# ADC3_FPGA_BGA.net
KiCad netlist of a schematic drawn in EAGLE
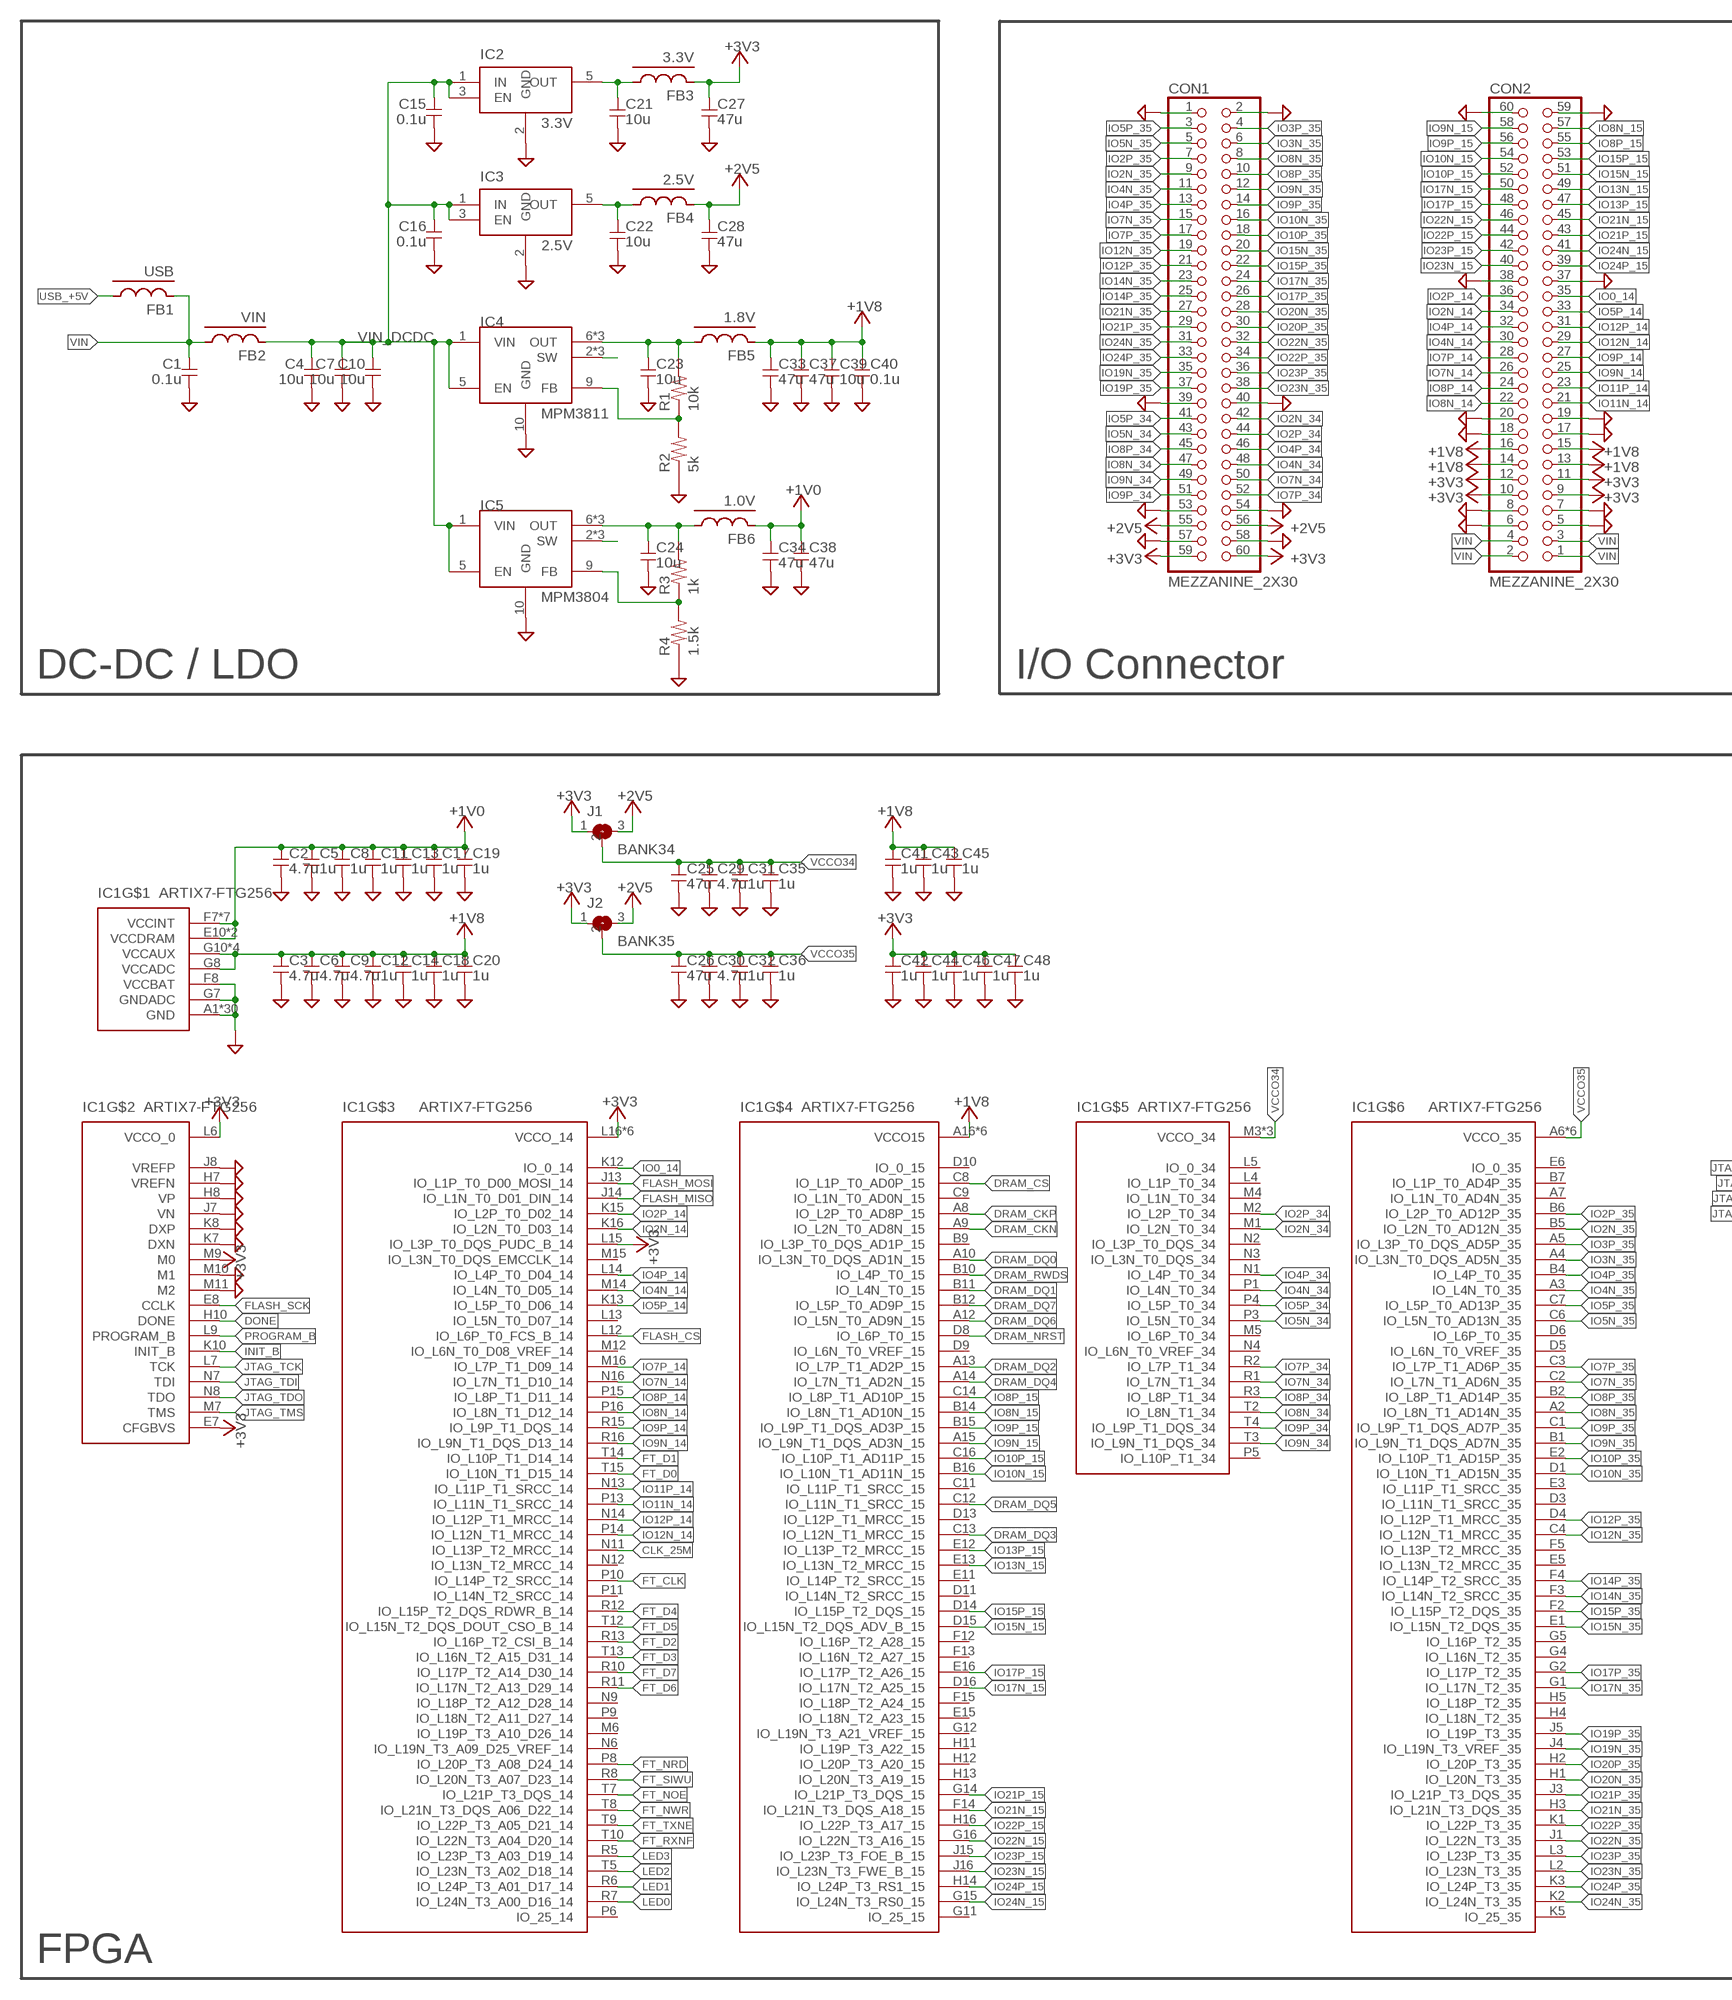
[diagram p0: schematic, sheet 1, part 1 of 2]
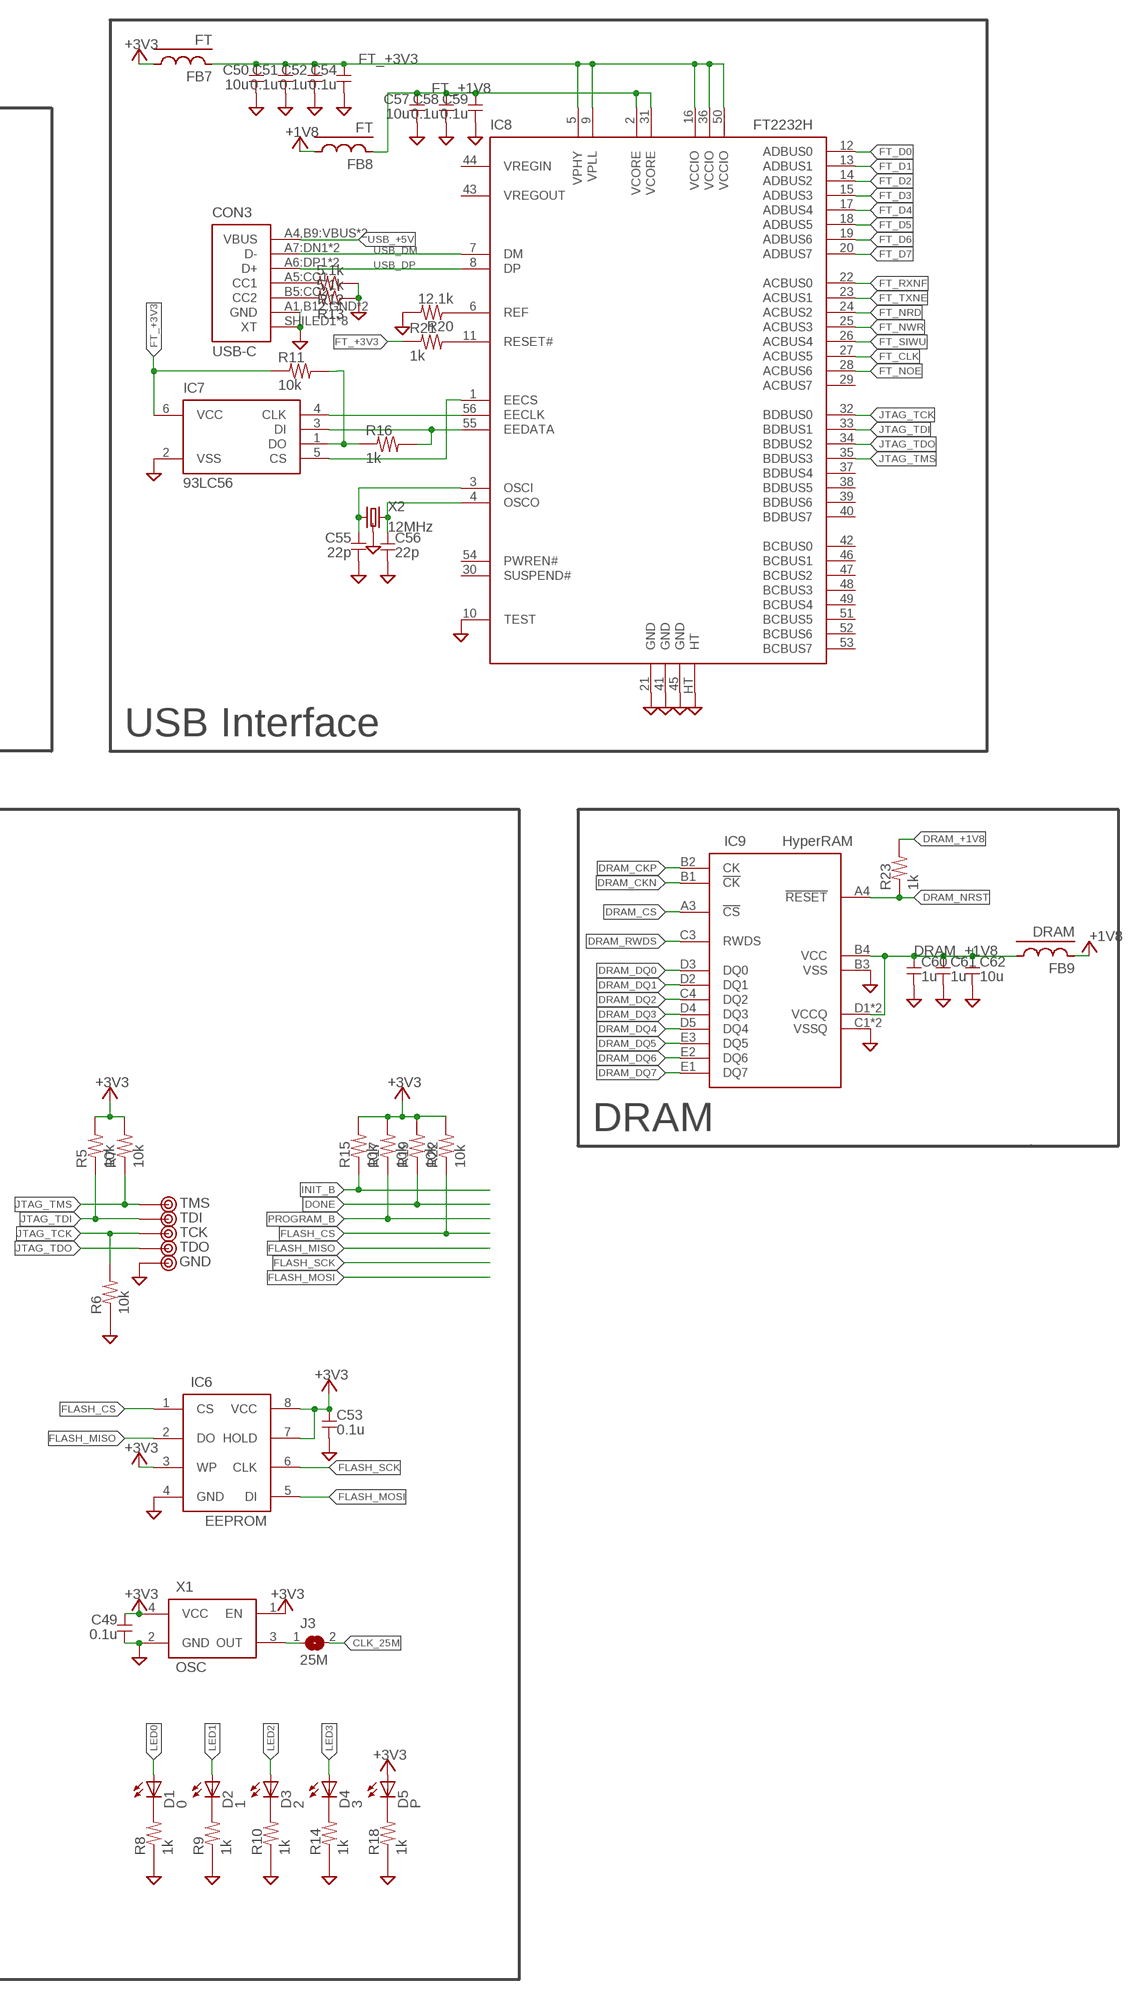
[diagram p1: schematic, sheet 1, part 2 of 2]

(export (version "E")
  (design (tool "Eeschema 10.0.6"))
  (components
    (comp (ref "C1")
      (value "0.1u")
      (footprint "eagle-import:1608C")
      (libsource (lib "eagle-import") (part "C-1608"))
    )
    (comp (ref "C2")
      (value "4.7u")
      (footprint "eagle-import:1608C")
      (libsource (lib "eagle-import") (part "C-1608"))
    )
    (comp (ref "C3")
      (value "4.7u")
      (footprint "eagle-import:1608C")
      (libsource (lib "eagle-import") (part "C-1608"))
    )
    (comp (ref "C4")
      (value "10u")
      (footprint "eagle-import:2012")
      (libsource (lib "eagle-import") (part "C-2012"))
    )
    (comp (ref "C5")
      (value "1u")
      (footprint "eagle-import:1005")
      (libsource (lib "eagle-import") (part "C-1005"))
    )
    (comp (ref "C6")
      (value "4.7u")
      (footprint "eagle-import:1608C")
      (libsource (lib "eagle-import") (part "C-1608"))
    )
    (comp (ref "C7")
      (value "10u")
      (footprint "eagle-import:1608C")
      (libsource (lib "eagle-import") (part "C-1608"))
    )
    (comp (ref "C8")
      (value "1u")
      (footprint "eagle-import:1005")
      (libsource (lib "eagle-import") (part "C-1005"))
    )
    (comp (ref "C9")
      (value "4.7u")
      (footprint "eagle-import:1608C")
      (libsource (lib "eagle-import") (part "C-1608"))
    )
    (comp (ref "C10")
      (value "10u")
      (footprint "eagle-import:1608C")
      (libsource (lib "eagle-import") (part "C-1608"))
    )
    (comp (ref "C11")
      (value "1u")
      (footprint "eagle-import:1005")
      (libsource (lib "eagle-import") (part "C-1005"))
    )
    (comp (ref "C12")
      (value "1u")
      (footprint "eagle-import:1005")
      (libsource (lib "eagle-import") (part "C-1005"))
    )
    (comp (ref "C13")
      (value "1u")
      (footprint "eagle-import:1005")
      (libsource (lib "eagle-import") (part "C-1005"))
    )
    (comp (ref "C14")
      (value "1u")
      (footprint "eagle-import:1005")
      (libsource (lib "eagle-import") (part "C-1005"))
    )
    (comp (ref "C15")
      (value "0.1u")
      (footprint "eagle-import:1608C")
      (libsource (lib "eagle-import") (part "C-1608"))
    )
    (comp (ref "C16")
      (value "0.1u")
      (footprint "eagle-import:1608C")
      (libsource (lib "eagle-import") (part "C-1608"))
    )
    (comp (ref "C17")
      (value "1u")
      (footprint "eagle-import:1005")
      (libsource (lib "eagle-import") (part "C-1005"))
    )
    (comp (ref "C18")
      (value "1u")
      (footprint "eagle-import:1005")
      (libsource (lib "eagle-import") (part "C-1005"))
    )
    (comp (ref "C19")
      (value "1u")
      (footprint "eagle-import:1005")
      (libsource (lib "eagle-import") (part "C-1005"))
    )
    (comp (ref "C20")
      (value "1u")
      (footprint "eagle-import:1005")
      (libsource (lib "eagle-import") (part "C-1005"))
    )
    (comp (ref "C21")
      (value "10u")
      (footprint "eagle-import:1608C")
      (libsource (lib "eagle-import") (part "C-1608"))
    )
    (comp (ref "C22")
      (value "10u")
      (footprint "eagle-import:1608C")
      (libsource (lib "eagle-import") (part "C-1608"))
    )
    (comp (ref "C23")
      (value "10u")
      (footprint "eagle-import:1608C")
      (libsource (lib "eagle-import") (part "C-1608"))
    )
    (comp (ref "C24")
      (value "10u")
      (footprint "eagle-import:1608C")
      (libsource (lib "eagle-import") (part "C-1608"))
    )
    (comp (ref "C25")
      (value "47u")
      (footprint "eagle-import:2012")
      (libsource (lib "eagle-import") (part "C-2012"))
    )
    (comp (ref "C26")
      (value "47u")
      (footprint "eagle-import:2012")
      (libsource (lib "eagle-import") (part "C-2012"))
    )
    (comp (ref "C27")
      (value "47u")
      (footprint "eagle-import:2012")
      (libsource (lib "eagle-import") (part "C-2012"))
    )
    (comp (ref "C28")
      (value "47u")
      (footprint "eagle-import:2012")
      (libsource (lib "eagle-import") (part "C-2012"))
    )
    (comp (ref "C29")
      (value "4.7u")
      (footprint "eagle-import:1608C")
      (libsource (lib "eagle-import") (part "C-1608"))
    )
    (comp (ref "C30")
      (value "4.7u")
      (footprint "eagle-import:1608C")
      (libsource (lib "eagle-import") (part "C-1608"))
    )
    (comp (ref "C31")
      (value "1u")
      (footprint "eagle-import:1005")
      (libsource (lib "eagle-import") (part "C-1005"))
    )
    (comp (ref "C32")
      (value "1u")
      (footprint "eagle-import:1005")
      (libsource (lib "eagle-import") (part "C-1005"))
    )
    (comp (ref "C33")
      (value "47u")
      (footprint "eagle-import:2012")
      (libsource (lib "eagle-import") (part "C-2012"))
    )
    (comp (ref "C34")
      (value "47u")
      (footprint "eagle-import:2012")
      (libsource (lib "eagle-import") (part "C-2012"))
    )
    (comp (ref "C35")
      (value "1u")
      (footprint "eagle-import:1005")
      (libsource (lib "eagle-import") (part "C-1005"))
    )
    (comp (ref "C36")
      (value "1u")
      (footprint "eagle-import:1005")
      (libsource (lib "eagle-import") (part "C-1005"))
    )
    (comp (ref "C37")
      (value "47u")
      (footprint "eagle-import:2012")
      (libsource (lib "eagle-import") (part "C-2012"))
    )
    (comp (ref "C38")
      (value "47u")
      (footprint "eagle-import:2012")
      (libsource (lib "eagle-import") (part "C-2012"))
    )
    (comp (ref "C39")
      (value "10u")
      (footprint "eagle-import:3216")
      (libsource (lib "eagle-import") (part "C-3216"))
    )
    (comp (ref "C40")
      (value "0.1u")
      (footprint "eagle-import:1608C")
      (libsource (lib "eagle-import") (part "C-1608"))
    )
    (comp (ref "C41")
      (value "1u")
      (footprint "eagle-import:1005")
      (libsource (lib "eagle-import") (part "C-1005"))
    )
    (comp (ref "C42")
      (value "1u")
      (footprint "eagle-import:1005")
      (libsource (lib "eagle-import") (part "C-1005"))
    )
    (comp (ref "C43")
      (value "1u")
      (footprint "eagle-import:1005")
      (libsource (lib "eagle-import") (part "C-1005"))
    )
    (comp (ref "C44")
      (value "1u")
      (footprint "eagle-import:1005")
      (libsource (lib "eagle-import") (part "C-1005"))
    )
    (comp (ref "C45")
      (value "1u")
      (footprint "eagle-import:1005")
      (libsource (lib "eagle-import") (part "C-1005"))
    )
    (comp (ref "C46")
      (value "1u")
      (footprint "eagle-import:1005")
      (libsource (lib "eagle-import") (part "C-1005"))
    )
    (comp (ref "C47")
      (value "1u")
      (footprint "eagle-import:1005")
      (libsource (lib "eagle-import") (part "C-1005"))
    )
    (comp (ref "C48")
      (value "1u")
      (footprint "eagle-import:1005")
      (libsource (lib "eagle-import") (part "C-1005"))
    )
    (comp (ref "C49")
      (value "0.1u")
      (footprint "eagle-import:1608C")
      (libsource (lib "eagle-import") (part "C-1608"))
    )
    (comp (ref "C50")
      (value "10u")
      (footprint "eagle-import:1608C")
      (libsource (lib "eagle-import") (part "C-1608"))
    )
    (comp (ref "C51")
      (value "0.1u")
      (footprint "eagle-import:1608C")
      (libsource (lib "eagle-import") (part "C-1608"))
    )
    (comp (ref "C52")
      (value "0.1u")
      (footprint "eagle-import:1608C")
      (libsource (lib "eagle-import") (part "C-1608"))
    )
    (comp (ref "C53")
      (value "0.1u")
      (footprint "eagle-import:1608C")
      (libsource (lib "eagle-import") (part "C-1608"))
    )
    (comp (ref "C54")
      (value "0.1u")
      (footprint "eagle-import:1608C")
      (libsource (lib "eagle-import") (part "C-1608"))
    )
    (comp (ref "C55")
      (value "22p")
      (footprint "eagle-import:1608C")
      (libsource (lib "eagle-import") (part "C-1608"))
    )
    (comp (ref "C56")
      (value "22p")
      (footprint "eagle-import:1608C")
      (libsource (lib "eagle-import") (part "C-1608"))
    )
    (comp (ref "C57")
      (value "10u")
      (footprint "eagle-import:1608C")
      (libsource (lib "eagle-import") (part "C-1608"))
    )
    (comp (ref "C58")
      (value "0.1u")
      (footprint "eagle-import:1608C")
      (libsource (lib "eagle-import") (part "C-1608"))
    )
    (comp (ref "C59")
      (value "0.1u")
      (footprint "eagle-import:1608C")
      (libsource (lib "eagle-import") (part "C-1608"))
    )
    (comp (ref "C60")
      (value "1u")
      (footprint "eagle-import:1608C")
      (libsource (lib "eagle-import") (part "C-1608"))
    )
    (comp (ref "C61")
      (value "1u")
      (footprint "eagle-import:1608C")
      (libsource (lib "eagle-import") (part "C-1608"))
    )
    (comp (ref "C62")
      (value "10u")
      (footprint "eagle-import:2012")
      (libsource (lib "eagle-import") (part "C-2012"))
    )
    (comp (ref "CON1")
      (value "MEZZANINE_2X30")
      (footprint "eagle-import:MEZZANINE_0.8MM_2X30")
      (libsource (lib "eagle-import") (part "MEZZANINE_2X30"))
    )
    (comp (ref "CON2")
      (value "MEZZANINE_2X30")
      (footprint "eagle-import:MEZZANINE_0.8MM_2X30")
      (libsource (lib "eagle-import") (part "MEZZANINE_2X30"))
    )
    (comp (ref "CON3")
      (value "USB-C")
      (footprint "eagle-import:5077CR-16-SMC2-BK-TR")
      (libsource (lib "eagle-import") (part "USB-C"))
    )
    (comp (ref "D1")
      (value "0")
      (footprint "eagle-import:D1608")
      (libsource (lib "eagle-import") (part "LED-SMD1608"))
    )
    (comp (ref "D2")
      (value "1")
      (footprint "eagle-import:D1608")
      (libsource (lib "eagle-import") (part "LED-SMD1608"))
    )
    (comp (ref "D3")
      (value "2")
      (footprint "eagle-import:D1608")
      (libsource (lib "eagle-import") (part "LED-SMD1608"))
    )
    (comp (ref "D4")
      (value "3")
      (footprint "eagle-import:D1608")
      (libsource (lib "eagle-import") (part "LED-SMD1608"))
    )
    (comp (ref "D5")
      (value "P")
      (footprint "eagle-import:D1608")
      (libsource (lib "eagle-import") (part "LED-SMD1608"))
    )
    (comp (ref "FB1")
      (value "USB")
      (footprint "eagle-import:1608-J")
      (libsource (lib "eagle-import") (part "FB"))
    )
    (comp (ref "FB2")
      (value "VIN")
      (footprint "eagle-import:1608-J")
      (libsource (lib "eagle-import") (part "FB"))
    )
    (comp (ref "FB3")
      (value "3.3V")
      (footprint "eagle-import:1608-J")
      (libsource (lib "eagle-import") (part "FB"))
    )
    (comp (ref "FB4")
      (value "2.5V")
      (footprint "eagle-import:1608-J")
      (libsource (lib "eagle-import") (part "FB"))
    )
    (comp (ref "FB5")
      (value "1.8V")
      (footprint "eagle-import:1608-J")
      (libsource (lib "eagle-import") (part "FB"))
    )
    (comp (ref "FB6")
      (value "1.0V")
      (footprint "eagle-import:1608-J")
      (libsource (lib "eagle-import") (part "FB"))
    )
    (comp (ref "FB7")
      (value "FT")
      (footprint "eagle-import:1608-J")
      (libsource (lib "eagle-import") (part "FB"))
    )
    (comp (ref "FB8")
      (value "FT")
      (footprint "eagle-import:1608-J")
      (libsource (lib "eagle-import") (part "FB"))
    )
    (comp (ref "FB9")
      (value "DRAM")
      (footprint "eagle-import:1608-J")
      (libsource (lib "eagle-import") (part "FB"))
    )
    (comp (ref "IC1")
      (value "ARTIX7-FTG256")
      (footprint "eagle-import:FTG256")
      (libsource (lib "eagle-import") (part "ARTIX7-FTG256"))
    )
    (comp (ref "IC2")
      (value "3.3V")
      (footprint "eagle-import:SOT23-5")
      (libsource (lib "eagle-import") (part "TLV740"))
    )
    (comp (ref "IC3")
      (value "2.5V")
      (footprint "eagle-import:SOT23-5")
      (libsource (lib "eagle-import") (part "TLV740"))
    )
    (comp (ref "IC4")
      (value "MPM3811")
      (footprint "eagle-import:QFN-10")
      (libsource (lib "eagle-import") (part "MPM3804"))
    )
    (comp (ref "IC5")
      (value "MPM3804")
      (footprint "eagle-import:QFN-10")
      (libsource (lib "eagle-import") (part "MPM3804"))
    )
    (comp (ref "IC6")
      (value "EEPROM")
      (footprint "eagle-import:SOIC-SOIJ-8")
      (libsource (lib "eagle-import") (part "EEPROM_SPI-WIDE"))
    )
    (comp (ref "IC7")
      (value "93LC56")
      (footprint "eagle-import:SOT23-6")
      (libsource (lib "eagle-import") (part "93LC56"))
    )
    (comp (ref "IC8")
      (value "FT2232H")
      (footprint "eagle-import:QFN56-HT")
      (libsource (lib "eagle-import") (part "FT2232H-2"))
    )
    (comp (ref "IC9")
      (value "HyperRAM")
      (footprint "eagle-import:TFBGA24")
      (libsource (lib "eagle-import") (part "HYPERRAM"))
    )
    (comp (ref "J1")
      (value "BANK34")
      (footprint "eagle-import:1608-3-J")
      (libsource (lib "eagle-import") (part "SJ-3-1608"))
    )
    (comp (ref "J2")
      (value "BANK35")
      (footprint "eagle-import:1608-3-J")
      (libsource (lib "eagle-import") (part "SJ-3-1608"))
    )
    (comp (ref "J3")
      (value "25M")
      (footprint "eagle-import:1608-J")
      (libsource (lib "eagle-import") (part "SJ-1608"))
    )
    (comp (ref "R1")
      (value "10k")
      (footprint "eagle-import:1608")
      (libsource (lib "eagle-import") (part "R-1608"))
    )
    (comp (ref "R2")
      (value "5k")
      (footprint "eagle-import:1608")
      (libsource (lib "eagle-import") (part "R-1608"))
    )
    (comp (ref "R3")
      (value "1k")
      (footprint "eagle-import:1608")
      (libsource (lib "eagle-import") (part "R-1608"))
    )
    (comp (ref "R4")
      (value "1.5k")
      (footprint "eagle-import:1608")
      (libsource (lib "eagle-import") (part "R-1608"))
    )
    (comp (ref "R5")
      (value "10k")
      (footprint "eagle-import:1608")
      (libsource (lib "eagle-import") (part "R-1608"))
    )
    (comp (ref "R6")
      (value "10k")
      (footprint "eagle-import:1608")
      (libsource (lib "eagle-import") (part "R-1608"))
    )
    (comp (ref "R7")
      (value "10k")
      (footprint "eagle-import:1608")
      (libsource (lib "eagle-import") (part "R-1608"))
    )
    (comp (ref "R8")
      (value "1k")
      (footprint "eagle-import:1608")
      (libsource (lib "eagle-import") (part "R-1608"))
    )
    (comp (ref "R9")
      (value "1k")
      (footprint "eagle-import:1608")
      (libsource (lib "eagle-import") (part "R-1608"))
    )
    (comp (ref "R10")
      (value "1k")
      (footprint "eagle-import:1608")
      (libsource (lib "eagle-import") (part "R-1608"))
    )
    (comp (ref "R11")
      (value "10k")
      (footprint "eagle-import:1608")
      (libsource (lib "eagle-import") (part "R-1608"))
    )
    (comp (ref "R12")
      (value "5.1k")
      (footprint "eagle-import:1608")
      (libsource (lib "eagle-import") (part "R-1608"))
    )
    (comp (ref "R13")
      (value "5.1k")
      (footprint "eagle-import:1608")
      (libsource (lib "eagle-import") (part "R-1608"))
    )
    (comp (ref "R14")
      (value "1k")
      (footprint "eagle-import:1608")
      (libsource (lib "eagle-import") (part "R-1608"))
    )
    (comp (ref "R15")
      (value "10k")
      (footprint "eagle-import:1608")
      (libsource (lib "eagle-import") (part "R-1608"))
    )
    (comp (ref "R16")
      (value "1k")
      (footprint "eagle-import:1608")
      (libsource (lib "eagle-import") (part "R-1608"))
    )
    (comp (ref "R17")
      (value "10k")
      (footprint "eagle-import:1608")
      (libsource (lib "eagle-import") (part "R-1608"))
    )
    (comp (ref "R18")
      (value "1k")
      (footprint "eagle-import:1608")
      (libsource (lib "eagle-import") (part "R-1608"))
    )
    (comp (ref "R19")
      (value "10k")
      (footprint "eagle-import:1608")
      (libsource (lib "eagle-import") (part "R-1608"))
    )
    (comp (ref "R20")
      (value "12.1k")
      (footprint "eagle-import:1608")
      (libsource (lib "eagle-import") (part "R-1608"))
    )
    (comp (ref "R21")
      (value "1k")
      (footprint "eagle-import:1608")
      (libsource (lib "eagle-import") (part "R-1608"))
    )
    (comp (ref "R22")
      (value "10k")
      (footprint "eagle-import:1608")
      (libsource (lib "eagle-import") (part "R-1608"))
    )
    (comp (ref "R23")
      (value "1k")
      (footprint "eagle-import:1608")
      (libsource (lib "eagle-import") (part "R-1608"))
    )
    (comp (ref "TP1")
      (value "TMS")
      (footprint "eagle-import:TESTPAD-SMALL")
      (libsource (lib "eagle-import") (part "TESTPIN-PAD-SMALL"))
    )
    (comp (ref "TP2")
      (value "TDI")
      (footprint "eagle-import:TESTPAD-SMALL")
      (libsource (lib "eagle-import") (part "TESTPIN-PAD-SMALL"))
    )
    (comp (ref "TP3")
      (value "TCK")
      (footprint "eagle-import:TESTPAD-SMALL")
      (libsource (lib "eagle-import") (part "TESTPIN-PAD-SMALL"))
    )
    (comp (ref "TP4")
      (value "TDO")
      (footprint "eagle-import:TESTPAD-SMALL")
      (libsource (lib "eagle-import") (part "TESTPIN-PAD-SMALL"))
    )
    (comp (ref "TP5")
      (value "GND")
      (footprint "eagle-import:TESTPAD-SMALL")
      (libsource (lib "eagle-import") (part "TESTPIN-PAD-SMALL"))
    )
    (comp (ref "X1")
      (value "OSC")
      (footprint "eagle-import:KC3225")
      (libsource (lib "eagle-import") (part "OSC-KC3225"))
    )
    (comp (ref "X2")
      (value "12MHz")
      (footprint "eagle-import:KC3225")
      (libsource (lib "eagle-import") (part "CRYSTAL2"))
    )
  )
  (nets
    (net (code "1") (name "+1V0") (class "Default")
      (node (ref "C11") (pin "1") (pinfunction "1_1") (pintype "passive"))
      (node (ref "C13") (pin "1") (pinfunction "1_1") (pintype "passive"))
      (node (ref "C17") (pin "1") (pinfunction "1_1") (pintype "passive"))
      (node (ref "C19") (pin "1") (pinfunction "1_1") (pintype "passive"))
      (node (ref "C2") (pin "1") (pinfunction "1_1") (pintype "passive"))
      (node (ref "C34") (pin "1") (pinfunction "1_1") (pintype "passive"))
      (node (ref "C38") (pin "1") (pinfunction "1_1") (pintype "passive"))
      (node (ref "C5") (pin "1") (pinfunction "1_1") (pintype "passive"))
      (node (ref "C8") (pin "1") (pinfunction "1_1") (pintype "passive"))
      (node (ref "FB6") (pin "2") (pinfunction "2_2") (pintype "passive"))
      (node (ref "IC1") (pin "E10") (pinfunction "VCCDRAM_E10") (pintype "input"))
      (node (ref "IC1") (pin "F11") (pinfunction "VCCDRAM_F11") (pintype "input"))
      (node (ref "IC1") (pin "F7") (pinfunction "VCCINT_F7") (pintype "input"))
      (node (ref "IC1") (pin "F9") (pinfunction "VCCINT_F9") (pintype "input"))
      (node (ref "IC1") (pin "G6") (pinfunction "VCCINT_G6") (pintype "input"))
      (node (ref "IC1") (pin "H9") (pinfunction "VCCINT_H9") (pintype "input"))
      (node (ref "IC1") (pin "J6") (pinfunction "VCCINT_J6") (pintype "input"))
      (node (ref "IC1") (pin "K9") (pinfunction "VCCINT_K9") (pintype "input"))
      (node (ref "IC1") (pin "L8") (pinfunction "VCCINT_L8") (pintype "input"))
    )
    (net (code "2") (name "+1V8") (class "Default")
      (node (ref "C12") (pin "1") (pinfunction "1_1") (pintype "passive"))
      (node (ref "C14") (pin "1") (pinfunction "1_1") (pintype "passive"))
      (node (ref "C18") (pin "1") (pinfunction "1_1") (pintype "passive"))
      (node (ref "C20") (pin "1") (pinfunction "1_1") (pintype "passive"))
      (node (ref "C3") (pin "1") (pinfunction "1_1") (pintype "passive"))
      (node (ref "C33") (pin "1") (pinfunction "1_1") (pintype "passive"))
      (node (ref "C37") (pin "1") (pinfunction "1_1") (pintype "passive"))
      (node (ref "C39") (pin "1") (pinfunction "1_1") (pintype "passive"))
      (node (ref "C40") (pin "1") (pinfunction "1_1") (pintype "passive"))
      (node (ref "C41") (pin "1") (pinfunction "1_1") (pintype "passive"))
      (node (ref "C43") (pin "1") (pinfunction "1_1") (pintype "passive"))
      (node (ref "C45") (pin "1") (pinfunction "1_1") (pintype "passive"))
      (node (ref "C6") (pin "1") (pinfunction "1_1") (pintype "passive"))
      (node (ref "C9") (pin "1") (pinfunction "1_1") (pintype "passive"))
      (node (ref "CON2") (pin "13") (pinfunction "13_13") (pintype "passive"))
      (node (ref "CON2") (pin "14") (pinfunction "14_14") (pintype "passive"))
      (node (ref "CON2") (pin "15") (pinfunction "15_15") (pintype "passive"))
      (node (ref "CON2") (pin "16") (pinfunction "16_16") (pintype "passive"))
      (node (ref "FB5") (pin "2") (pinfunction "2_2") (pintype "passive"))
      (node (ref "FB8") (pin "1") (pinfunction "1_1") (pintype "passive"))
      (node (ref "FB9") (pin "2") (pinfunction "2_2") (pintype "passive"))
      (node (ref "IC1") (pin "A16") (pinfunction "VCCO15_A16") (pintype "input"))
      (node (ref "IC1") (pin "B13") (pinfunction "VCCO15_B13") (pintype "input"))
      (node (ref "IC1") (pin "C10") (pinfunction "VCCO15_C10") (pintype "input"))
      (node (ref "IC1") (pin "E14") (pinfunction "VCCO15_E14") (pintype "input"))
      (node (ref "IC1") (pin "G10") (pinfunction "VCCAUX_G10") (pintype "input"))
      (node (ref "IC1") (pin "G8") (pinfunction "VCCADC_G8") (pintype "input"))
      (node (ref "IC1") (pin "H15") (pinfunction "VCCO15_H15") (pintype "input"))
      (node (ref "IC1") (pin "J10") (pinfunction "VCCAUX_J10") (pintype "input"))
      (node (ref "IC1") (pin "J12") (pinfunction "VCCO15_J12") (pintype "input"))
      (node (ref "IC1") (pin "K11") (pinfunction "VCCAUX_K11") (pintype "input"))
      (node (ref "IC1") (pin "L10") (pinfunction "VCCAUX_L10") (pintype "input"))
    )
    (net (code "3") (name "+2V5") (class "Default")
      (node (ref "C28") (pin "1") (pinfunction "1_1") (pintype "passive"))
      (node (ref "CON1") (pin "55") (pinfunction "55_55") (pintype "passive"))
      (node (ref "CON1") (pin "56") (pinfunction "56_56") (pintype "passive"))
      (node (ref "FB4") (pin "2") (pinfunction "2_2") (pintype "passive"))
      (node (ref "J1") (pin "3") (pinfunction "3_3") (pintype "passive"))
      (node (ref "J2") (pin "3") (pinfunction "3_3") (pintype "passive"))
    )
    (net (code "4") (name "+3V3") (class "Default")
      (node (ref "C27") (pin "1") (pinfunction "1_1") (pintype "passive"))
      (node (ref "C42") (pin "1") (pinfunction "1_1") (pintype "passive"))
      (node (ref "C44") (pin "1") (pinfunction "1_1") (pintype "passive"))
      (node (ref "C46") (pin "1") (pinfunction "1_1") (pintype "passive"))
      (node (ref "C47") (pin "1") (pinfunction "1_1") (pintype "passive"))
      (node (ref "C48") (pin "1") (pinfunction "1_1") (pintype "passive"))
      (node (ref "C49") (pin "1") (pinfunction "1_1") (pintype "passive"))
      (node (ref "C53") (pin "1") (pinfunction "1_1") (pintype "passive"))
      (node (ref "CON1") (pin "59") (pinfunction "59_59") (pintype "passive"))
      (node (ref "CON1") (pin "60") (pinfunction "60_60") (pintype "passive"))
      (node (ref "CON2") (pin "10") (pinfunction "10_10") (pintype "passive"))
      (node (ref "CON2") (pin "11") (pinfunction "11_11") (pintype "passive"))
      (node (ref "CON2") (pin "12") (pinfunction "12_12") (pintype "passive"))
      (node (ref "CON2") (pin "9") (pinfunction "9_9") (pintype "passive"))
      (node (ref "D5") (pin "A") (pinfunction "A_A") (pintype "passive"))
      (node (ref "FB3") (pin "2") (pinfunction "2_2") (pintype "passive"))
      (node (ref "FB7") (pin "1") (pinfunction "1_1") (pintype "passive"))
      (node (ref "IC1") (pin "E7") (pinfunction "CFGBVS_E7") (pintype "bidirectional"))
      (node (ref "IC1") (pin "L15") (pinfunction "IO_L3P_T0_DQS_PUDC_B_14_L15") (pintype "bidirectional"))
      (node (ref "IC1") (pin "L16") (pinfunction "VCCO_14_L16") (pintype "input"))
      (node (ref "IC1") (pin "L6") (pinfunction "VCCO_0_L6") (pintype "bidirectional"))
      (node (ref "IC1") (pin "M13") (pinfunction "VCCO_14_M13") (pintype "input"))
      (node (ref "IC1") (pin "M9") (pinfunction "M0_M9") (pintype "bidirectional"))
      (node (ref "IC1") (pin "N10") (pinfunction "VCCO_14_N10") (pintype "input"))
      (node (ref "IC1") (pin "P7") (pinfunction "VCCO_14_P7") (pintype "input"))
      (node (ref "IC1") (pin "R14") (pinfunction "VCCO_14_R14") (pintype "input"))
      (node (ref "IC1") (pin "T11") (pinfunction "VCCO_14_T11") (pintype "input"))
      (node (ref "IC6") (pin "3") (pinfunction "WP_3") (pintype "input"))
      (node (ref "IC6") (pin "7") (pinfunction "HOLD_7") (pintype "input"))
      (node (ref "IC6") (pin "8") (pinfunction "VCC_8") (pintype "input"))
      (node (ref "J1") (pin "1") (pinfunction "1_1") (pintype "passive"))
      (node (ref "J2") (pin "1") (pinfunction "1_1") (pintype "passive"))
      (node (ref "R15") (pin "2") (pinfunction "2_2") (pintype "passive"))
      (node (ref "R17") (pin "2") (pinfunction "2_2") (pintype "passive"))
      (node (ref "R19") (pin "2") (pinfunction "2_2") (pintype "passive"))
      (node (ref "R22") (pin "2") (pinfunction "2_2") (pintype "passive"))
      (node (ref "R5") (pin "2") (pinfunction "2_2") (pintype "passive"))
      (node (ref "R7") (pin "2") (pinfunction "2_2") (pintype "passive"))
      (node (ref "X1") (pin "1") (pinfunction "EN_1") (pintype "input"))
      (node (ref "X1") (pin "4") (pinfunction "VCC_4") (pintype "input"))
    )
    (net (code "5") (name "/FT_+1V8") (class "Default")
      (node (ref "C57") (pin "1") (pinfunction "1_1") (pintype "passive"))
      (node (ref "C58") (pin "1") (pinfunction "1_1") (pintype "passive"))
      (node (ref "C59") (pin "1") (pinfunction "1_1") (pintype "passive"))
      (node (ref "FB8") (pin "2") (pinfunction "2_2") (pintype "passive"))
      (node (ref "IC8") (pin "2") (pinfunction "VCORE_2") (pintype "input"))
      (node (ref "IC8") (pin "31") (pinfunction "VCORE_31") (pintype "input"))
    )
    (net (code "6") (name "/USB_DM") (class "Default")
      (node (ref "CON3") (pin "A7:DN1") (pinfunction "D-_A7:DN1") (pintype "bidirectional"))
      (node (ref "CON3") (pin "B7:DN2") (pinfunction "D-_B7:DN2") (pintype "bidirectional"))
      (node (ref "IC8") (pin "7") (pinfunction "DM_7") (pintype "bidirectional"))
    )
    (net (code "7") (name "/USB_DP") (class "Default")
      (node (ref "CON3") (pin "A6:DP1") (pinfunction "D+_A6:DP1") (pintype "bidirectional"))
      (node (ref "CON3") (pin "B6:DP2") (pinfunction "D+_B6:DP2") (pintype "bidirectional"))
      (node (ref "IC8") (pin "8") (pinfunction "DP_8") (pintype "bidirectional"))
    )
    (net (code "8") (name "/VIN_DCDC") (class "Default")
      (node (ref "C10") (pin "1") (pinfunction "1_1") (pintype "passive"))
      (node (ref "C15") (pin "1") (pinfunction "1_1") (pintype "passive"))
      (node (ref "C16") (pin "1") (pinfunction "1_1") (pintype "passive"))
      (node (ref "C4") (pin "1") (pinfunction "1_1") (pintype "passive"))
      (node (ref "C7") (pin "1") (pinfunction "1_1") (pintype "passive"))
      (node (ref "FB2") (pin "2") (pinfunction "2_2") (pintype "passive"))
      (node (ref "IC2") (pin "1") (pinfunction "IN_1") (pintype "input"))
      (node (ref "IC2") (pin "3") (pinfunction "EN_3") (pintype "input"))
      (node (ref "IC3") (pin "1") (pinfunction "IN_1") (pintype "input"))
      (node (ref "IC3") (pin "3") (pinfunction "EN_3") (pintype "input"))
      (node (ref "IC4") (pin "1") (pinfunction "VIN_1") (pintype "input"))
      (node (ref "IC4") (pin "5") (pinfunction "EN_5") (pintype "input"))
      (node (ref "IC5") (pin "1") (pinfunction "VIN_1") (pintype "input"))
      (node (ref "IC5") (pin "5") (pinfunction "EN_5") (pintype "input"))
    )
    (net (code "9") (name "CLK_25M") (class "Default")
      (node (ref "IC1") (pin "N11") (pinfunction "IO_L13P_T2_MRCC_14_N11") (pintype "bidirectional"))
      (node (ref "J3") (pin "2") (pinfunction "2_2") (pintype "passive"))
    )
    (net (code "10") (name "DONE") (class "Default")
      (node (ref "IC1") (pin "H10") (pinfunction "DONE_H10") (pintype "bidirectional"))
      (node (ref "R19") (pin "1") (pinfunction "1_1") (pintype "passive"))
    )
    (net (code "11") (name "DRAM_+1V8") (class "Default")
      (node (ref "C60") (pin "1") (pinfunction "1_1") (pintype "passive"))
      (node (ref "C61") (pin "1") (pinfunction "1_1") (pintype "passive"))
      (node (ref "C62") (pin "1") (pinfunction "1_1") (pintype "passive"))
      (node (ref "FB9") (pin "1") (pinfunction "1_1") (pintype "passive"))
      (node (ref "IC9") (pin "B4") (pinfunction "VCC_B4") (pintype "input"))
      (node (ref "IC9") (pin "D1") (pinfunction "VCCQ_D1") (pintype "input"))
      (node (ref "IC9") (pin "E4") (pinfunction "VCCQ_E4") (pintype "input"))
      (node (ref "R23") (pin "2") (pinfunction "2_2") (pintype "passive"))
    )
    (net (code "12") (name "DRAM_CKN") (class "Default")
      (node (ref "IC1") (pin "A9") (pinfunction "IO_L2N_T0_AD8N_15_A9") (pintype "bidirectional"))
      (node (ref "IC9") (pin "B1") (pinfunction "~{CK}_B1") (pintype "input"))
    )
    (net (code "13") (name "DRAM_CKP") (class "Default")
      (node (ref "IC1") (pin "A8") (pinfunction "IO_L2P_T0_AD8P_15_A8") (pintype "bidirectional"))
      (node (ref "IC9") (pin "B2") (pinfunction "CK_B2") (pintype "input"))
    )
    (net (code "14") (name "DRAM_CS") (class "Default")
      (node (ref "IC1") (pin "C8") (pinfunction "IO_L1P_T0_AD0P_15_C8") (pintype "bidirectional"))
      (node (ref "IC9") (pin "A3") (pinfunction "~{CS}_A3") (pintype "input"))
    )
    (net (code "15") (name "DRAM_DQ0") (class "Default")
      (node (ref "IC1") (pin "A10") (pinfunction "IO_L3N_T0_DQS_AD1N_15_A10") (pintype "bidirectional"))
      (node (ref "IC9") (pin "D3") (pinfunction "DQ0_D3") (pintype "bidirectional"))
    )
    (net (code "16") (name "DRAM_DQ1") (class "Default")
      (node (ref "IC1") (pin "B11") (pinfunction "IO_L4N_T0_15_B11") (pintype "bidirectional"))
      (node (ref "IC9") (pin "D2") (pinfunction "DQ1_D2") (pintype "bidirectional"))
    )
    (net (code "17") (name "DRAM_DQ2") (class "Default")
      (node (ref "IC1") (pin "A13") (pinfunction "IO_L7P_T1_AD2P_15_A13") (pintype "bidirectional"))
      (node (ref "IC9") (pin "C4") (pinfunction "DQ2_C4") (pintype "bidirectional"))
    )
    (net (code "18") (name "DRAM_DQ3") (class "Default")
      (node (ref "IC1") (pin "C13") (pinfunction "IO_L12N_T1_MRCC_15_C13") (pintype "bidirectional"))
      (node (ref "IC9") (pin "D4") (pinfunction "DQ3_D4") (pintype "bidirectional"))
    )
    (net (code "19") (name "DRAM_DQ4") (class "Default")
      (node (ref "IC1") (pin "A14") (pinfunction "IO_L7N_T1_AD2N_15_A14") (pintype "bidirectional"))
      (node (ref "IC9") (pin "D5") (pinfunction "DQ4_D5") (pintype "bidirectional"))
    )
    (net (code "20") (name "DRAM_DQ5") (class "Default")
      (node (ref "IC1") (pin "C12") (pinfunction "IO_L11N_T1_SRCC_15_C12") (pintype "bidirectional"))
      (node (ref "IC9") (pin "E3") (pinfunction "DQ5_E3") (pintype "bidirectional"))
    )
    (net (code "21") (name "DRAM_DQ6") (class "Default")
      (node (ref "IC1") (pin "A12") (pinfunction "IO_L5N_T0_AD9N_15_A12") (pintype "bidirectional"))
      (node (ref "IC9") (pin "E2") (pinfunction "DQ6_E2") (pintype "bidirectional"))
    )
    (net (code "22") (name "DRAM_DQ7") (class "Default")
      (node (ref "IC1") (pin "B12") (pinfunction "IO_L5P_T0_AD9P_15_B12") (pintype "bidirectional"))
      (node (ref "IC9") (pin "E1") (pinfunction "DQ7_E1") (pintype "bidirectional"))
    )
    (net (code "23") (name "DRAM_NRST") (class "Default")
      (node (ref "IC1") (pin "D8") (pinfunction "IO_L6P_T0_15_D8") (pintype "bidirectional"))
      (node (ref "IC9") (pin "A4") (pinfunction "~{RESET}_A4") (pintype "input"))
      (node (ref "R23") (pin "1") (pinfunction "1_1") (pintype "passive"))
    )
    (net (code "24") (name "DRAM_RWDS") (class "Default")
      (node (ref "IC1") (pin "B10") (pinfunction "IO_L4P_T0_15_B10") (pintype "bidirectional"))
      (node (ref "IC9") (pin "C3") (pinfunction "RWDS_C3") (pintype "bidirectional"))
    )
    (net (code "25") (name "FLASH_CS") (class "Default")
      (node (ref "IC1") (pin "L12") (pinfunction "IO_L6P_T0_FCS_B_14_L12") (pintype "bidirectional"))
      (node (ref "IC6") (pin "1") (pinfunction "CS_1") (pintype "input"))
      (node (ref "R22") (pin "1") (pinfunction "1_1") (pintype "passive"))
    )
    (net (code "26") (name "FLASH_MISO") (class "Default")
      (node (ref "IC1") (pin "J14") (pinfunction "IO_L1N_T0_D01_DIN_14_J14") (pintype "bidirectional"))
      (node (ref "IC6") (pin "2") (pinfunction "DO_2") (pintype "output"))
    )
    (net (code "27") (name "FLASH_MOSI") (class "Default")
      (node (ref "IC1") (pin "J13") (pinfunction "IO_L1P_T0_D00_MOSI_14_J13") (pintype "bidirectional"))
      (node (ref "IC6") (pin "5") (pinfunction "DI_5") (pintype "input"))
    )
    (net (code "28") (name "FLASH_SCK") (class "Default")
      (node (ref "IC1") (pin "E8") (pinfunction "CCLK_E8") (pintype "bidirectional"))
      (node (ref "IC6") (pin "6") (pinfunction "CLK_6") (pintype "input"))
    )
    (net (code "29") (name "FT_+3V3") (class "Default")
      (node (ref "C50") (pin "1") (pinfunction "1_1") (pintype "passive"))
      (node (ref "C51") (pin "1") (pinfunction "1_1") (pintype "passive"))
      (node (ref "C52") (pin "1") (pinfunction "1_1") (pintype "passive"))
      (node (ref "C54") (pin "1") (pinfunction "1_1") (pintype "passive"))
      (node (ref "FB7") (pin "2") (pinfunction "2_2") (pintype "passive"))
      (node (ref "IC7") (pin "6") (pinfunction "VCC_6") (pintype "input"))
      (node (ref "IC8") (pin "16") (pinfunction "VCCIO_16") (pintype "input"))
      (node (ref "IC8") (pin "36") (pinfunction "VCCIO_36") (pintype "input"))
      (node (ref "IC8") (pin "5") (pinfunction "VPHY_5") (pintype "input"))
      (node (ref "IC8") (pin "50") (pinfunction "VCCIO_50") (pintype "input"))
      (node (ref "IC8") (pin "9") (pinfunction "VPLL_9") (pintype "input"))
      (node (ref "R11") (pin "1") (pinfunction "1_1") (pintype "passive"))
      (node (ref "R21") (pin "1") (pinfunction "1_1") (pintype "passive"))
    )
    (net (code "30") (name "FT_CLK") (class "Default")
      (node (ref "IC1") (pin "P10") (pinfunction "IO_L14P_T2_SRCC_14_P10") (pintype "bidirectional"))
      (node (ref "IC8") (pin "27") (pinfunction "ACBUS5_27") (pintype "bidirectional"))
    )
    (net (code "31") (name "FT_D0") (class "Default")
      (node (ref "IC1") (pin "T15") (pinfunction "IO_L10N_T1_D15_14_T15") (pintype "bidirectional"))
      (node (ref "IC8") (pin "12") (pinfunction "ADBUS0_12") (pintype "bidirectional"))
    )
    (net (code "32") (name "FT_D1") (class "Default")
      (node (ref "IC1") (pin "T14") (pinfunction "IO_L10P_T1_D14_14_T14") (pintype "bidirectional"))
      (node (ref "IC8") (pin "13") (pinfunction "ADBUS1_13") (pintype "bidirectional"))
    )
    (net (code "33") (name "FT_D2") (class "Default")
      (node (ref "IC1") (pin "R13") (pinfunction "IO_L16P_T2_CSI_B_14_R13") (pintype "bidirectional"))
      (node (ref "IC8") (pin "14") (pinfunction "ADBUS2_14") (pintype "bidirectional"))
    )
    (net (code "34") (name "FT_D3") (class "Default")
      (node (ref "IC1") (pin "T13") (pinfunction "IO_L16N_T2_A15_D31_14_T13") (pintype "bidirectional"))
      (node (ref "IC8") (pin "15") (pinfunction "ADBUS3_15") (pintype "bidirectional"))
    )
    (net (code "35") (name "FT_D4") (class "Default")
      (node (ref "IC1") (pin "R12") (pinfunction "IO_L15P_T2_DQS_RDWR_B_14_R12") (pintype "bidirectional"))
      (node (ref "IC8") (pin "17") (pinfunction "ADBUS4_17") (pintype "bidirectional"))
    )
    (net (code "36") (name "FT_D5") (class "Default")
      (node (ref "IC1") (pin "T12") (pinfunction "IO_L15N_T2_DQS_DOUT_CSO_B_14_T12") (pintype "bidirectional"))
      (node (ref "IC8") (pin "18") (pinfunction "ADBUS5_18") (pintype "bidirectional"))
    )
    (net (code "37") (name "FT_D6") (class "Default")
      (node (ref "IC1") (pin "R11") (pinfunction "IO_L17N_T2_A13_D29_14_R11") (pintype "bidirectional"))
      (node (ref "IC8") (pin "19") (pinfunction "ADBUS6_19") (pintype "bidirectional"))
    )
    (net (code "38") (name "FT_D7") (class "Default")
      (node (ref "IC1") (pin "R10") (pinfunction "IO_L17P_T2_A14_D30_14_R10") (pintype "bidirectional"))
      (node (ref "IC8") (pin "20") (pinfunction "ADBUS7_20") (pintype "bidirectional"))
    )
    (net (code "39") (name "FT_NOE") (class "Default")
      (node (ref "IC1") (pin "T7") (pinfunction "IO_L21P_T3_DQS_14_T7") (pintype "bidirectional"))
      (node (ref "IC8") (pin "28") (pinfunction "ACBUS6_28") (pintype "bidirectional"))
    )
    (net (code "40") (name "FT_NRD") (class "Default")
      (node (ref "IC1") (pin "P8") (pinfunction "IO_L20P_T3_A08_D24_14_P8") (pintype "bidirectional"))
      (node (ref "IC8") (pin "24") (pinfunction "ACBUS2_24") (pintype "bidirectional"))
    )
    (net (code "41") (name "FT_NWR") (class "Default")
      (node (ref "IC1") (pin "T8") (pinfunction "IO_L21N_T3_DQS_A06_D22_14_T8") (pintype "bidirectional"))
      (node (ref "IC8") (pin "25") (pinfunction "ACBUS3_25") (pintype "bidirectional"))
    )
    (net (code "42") (name "FT_RXNF") (class "Default")
      (node (ref "IC1") (pin "T10") (pinfunction "IO_L22N_T3_A04_D20_14_T10") (pintype "bidirectional"))
      (node (ref "IC8") (pin "22") (pinfunction "ACBUS0_22") (pintype "bidirectional"))
    )
    (net (code "43") (name "FT_SIWU") (class "Default")
      (node (ref "IC1") (pin "R8") (pinfunction "IO_L20N_T3_A07_D23_14_R8") (pintype "bidirectional"))
      (node (ref "IC8") (pin "26") (pinfunction "ACBUS4_26") (pintype "bidirectional"))
    )
    (net (code "44") (name "FT_TXNE") (class "Default")
      (node (ref "IC1") (pin "T9") (pinfunction "IO_L22P_T3_A05_D21_14_T9") (pintype "bidirectional"))
      (node (ref "IC8") (pin "23") (pinfunction "ACBUS1_23") (pintype "bidirectional"))
    )
    (net (code "45") (name "GND") (class "Default")
      (node (ref "C1") (pin "2") (pinfunction "2_2") (pintype "passive"))
      (node (ref "C10") (pin "2") (pinfunction "2_2") (pintype "passive"))
      (node (ref "C11") (pin "2") (pinfunction "2_2") (pintype "passive"))
      (node (ref "C12") (pin "2") (pinfunction "2_2") (pintype "passive"))
      (node (ref "C13") (pin "2") (pinfunction "2_2") (pintype "passive"))
      (node (ref "C14") (pin "2") (pinfunction "2_2") (pintype "passive"))
      (node (ref "C15") (pin "2") (pinfunction "2_2") (pintype "passive"))
      (node (ref "C16") (pin "2") (pinfunction "2_2") (pintype "passive"))
      (node (ref "C17") (pin "2") (pinfunction "2_2") (pintype "passive"))
      (node (ref "C18") (pin "2") (pinfunction "2_2") (pintype "passive"))
      (node (ref "C19") (pin "2") (pinfunction "2_2") (pintype "passive"))
      (node (ref "C2") (pin "2") (pinfunction "2_2") (pintype "passive"))
      (node (ref "C20") (pin "2") (pinfunction "2_2") (pintype "passive"))
      (node (ref "C21") (pin "2") (pinfunction "2_2") (pintype "passive"))
      (node (ref "C22") (pin "2") (pinfunction "2_2") (pintype "passive"))
      (node (ref "C23") (pin "2") (pinfunction "2_2") (pintype "passive"))
      (node (ref "C24") (pin "2") (pinfunction "2_2") (pintype "passive"))
      (node (ref "C25") (pin "2") (pinfunction "2_2") (pintype "passive"))
      (node (ref "C26") (pin "2") (pinfunction "2_2") (pintype "passive"))
      (node (ref "C27") (pin "2") (pinfunction "2_2") (pintype "passive"))
      (node (ref "C28") (pin "2") (pinfunction "2_2") (pintype "passive"))
      (node (ref "C29") (pin "2") (pinfunction "2_2") (pintype "passive"))
      (node (ref "C3") (pin "2") (pinfunction "2_2") (pintype "passive"))
      (node (ref "C30") (pin "2") (pinfunction "2_2") (pintype "passive"))
      (node (ref "C31") (pin "2") (pinfunction "2_2") (pintype "passive"))
      (node (ref "C32") (pin "2") (pinfunction "2_2") (pintype "passive"))
      (node (ref "C33") (pin "2") (pinfunction "2_2") (pintype "passive"))
      (node (ref "C34") (pin "2") (pinfunction "2_2") (pintype "passive"))
      (node (ref "C35") (pin "2") (pinfunction "2_2") (pintype "passive"))
      (node (ref "C36") (pin "2") (pinfunction "2_2") (pintype "passive"))
      (node (ref "C37") (pin "2") (pinfunction "2_2") (pintype "passive"))
      (node (ref "C38") (pin "2") (pinfunction "2_2") (pintype "passive"))
      (node (ref "C39") (pin "2") (pinfunction "2_2") (pintype "passive"))
      (node (ref "C4") (pin "2") (pinfunction "2_2") (pintype "passive"))
      (node (ref "C40") (pin "2") (pinfunction "2_2") (pintype "passive"))
      (node (ref "C41") (pin "2") (pinfunction "2_2") (pintype "passive"))
      (node (ref "C42") (pin "2") (pinfunction "2_2") (pintype "passive"))
      (node (ref "C43") (pin "2") (pinfunction "2_2") (pintype "passive"))
      (node (ref "C44") (pin "2") (pinfunction "2_2") (pintype "passive"))
      (node (ref "C45") (pin "2") (pinfunction "2_2") (pintype "passive"))
      (node (ref "C46") (pin "2") (pinfunction "2_2") (pintype "passive"))
      (node (ref "C47") (pin "2") (pinfunction "2_2") (pintype "passive"))
      (node (ref "C48") (pin "2") (pinfunction "2_2") (pintype "passive"))
      (node (ref "C49") (pin "2") (pinfunction "2_2") (pintype "passive"))
      (node (ref "C5") (pin "2") (pinfunction "2_2") (pintype "passive"))
      (node (ref "C50") (pin "2") (pinfunction "2_2") (pintype "passive"))
      (node (ref "C51") (pin "2") (pinfunction "2_2") (pintype "passive"))
      (node (ref "C52") (pin "2") (pinfunction "2_2") (pintype "passive"))
      (node (ref "C53") (pin "2") (pinfunction "2_2") (pintype "passive"))
      (node (ref "C54") (pin "2") (pinfunction "2_2") (pintype "passive"))
      (node (ref "C55") (pin "2") (pinfunction "2_2") (pintype "passive"))
      (node (ref "C56") (pin "2") (pinfunction "2_2") (pintype "passive"))
      (node (ref "C57") (pin "2") (pinfunction "2_2") (pintype "passive"))
      (node (ref "C58") (pin "2") (pinfunction "2_2") (pintype "passive"))
      (node (ref "C59") (pin "2") (pinfunction "2_2") (pintype "passive"))
      (node (ref "C6") (pin "2") (pinfunction "2_2") (pintype "passive"))
      (node (ref "C60") (pin "2") (pinfunction "2_2") (pintype "passive"))
      (node (ref "C61") (pin "2") (pinfunction "2_2") (pintype "passive"))
      (node (ref "C62") (pin "2") (pinfunction "2_2") (pintype "passive"))
      (node (ref "C7") (pin "2") (pinfunction "2_2") (pintype "passive"))
      (node (ref "C8") (pin "2") (pinfunction "2_2") (pintype "passive"))
      (node (ref "C9") (pin "2") (pinfunction "2_2") (pintype "passive"))
      (node (ref "CON1") (pin "1") (pinfunction "1_1") (pintype "passive"))
      (node (ref "CON1") (pin "2") (pinfunction "2_2") (pintype "passive"))
      (node (ref "CON1") (pin "39") (pinfunction "39_39") (pintype "passive"))
      (node (ref "CON1") (pin "40") (pinfunction "40_40") (pintype "passive"))
      (node (ref "CON1") (pin "53") (pinfunction "53_53") (pintype "passive"))
      (node (ref "CON1") (pin "54") (pinfunction "54_54") (pintype "passive"))
      (node (ref "CON1") (pin "57") (pinfunction "57_57") (pintype "passive"))
      (node (ref "CON1") (pin "58") (pinfunction "58_58") (pintype "passive"))
      (node (ref "CON2") (pin "17") (pinfunction "17_17") (pintype "passive"))
      (node (ref "CON2") (pin "18") (pinfunction "18_18") (pintype "passive"))
      (node (ref "CON2") (pin "19") (pinfunction "19_19") (pintype "passive"))
      (node (ref "CON2") (pin "20") (pinfunction "20_20") (pintype "passive"))
      (node (ref "CON2") (pin "37") (pinfunction "37_37") (pintype "passive"))
      (node (ref "CON2") (pin "38") (pinfunction "38_38") (pintype "passive"))
      (node (ref "CON2") (pin "5") (pinfunction "5_5") (pintype "passive"))
      (node (ref "CON2") (pin "59") (pinfunction "59_59") (pintype "passive"))
      (node (ref "CON2") (pin "6") (pinfunction "6_6") (pintype "passive"))
      (node (ref "CON2") (pin "60") (pinfunction "60_60") (pintype "passive"))
      (node (ref "CON2") (pin "7") (pinfunction "7_7") (pintype "passive"))
      (node (ref "CON2") (pin "8") (pinfunction "8_8") (pintype "passive"))
      (node (ref "CON3") (pin "A1,B12:GND") (pinfunction "GND_A1,B12:GND") (pintype "bidirectional"))
      (node (ref "CON3") (pin "B1,A12:GND") (pinfunction "GND_B1,A12:GND") (pintype "bidirectional"))
      (node (ref "CON3") (pin "SHILED1") (pinfunction "XT_SHILED1") (pintype "bidirectional"))
      (node (ref "CON3") (pin "SHILED2") (pinfunction "XT_SHILED2") (pintype "bidirectional"))
      (node (ref "CON3") (pin "SHILED3") (pinfunction "XT_SHILED3") (pintype "bidirectional"))
      (node (ref "CON3") (pin "SHILED4") (pinfunction "XT_SHILED4") (pintype "bidirectional"))
      (node (ref "CON3") (pin "SHILED5") (pinfunction "XT_SHILED5") (pintype "bidirectional"))
      (node (ref "CON3") (pin "SHILED6") (pinfunction "XT_SHILED6") (pintype "bidirectional"))
      (node (ref "CON3") (pin "SHILED7") (pinfunction "XT_SHILED7") (pintype "bidirectional"))
      (node (ref "CON3") (pin "SHILED8") (pinfunction "XT_SHILED8") (pintype "bidirectional"))
      (node (ref "IC1") (pin "A1") (pinfunction "GND_A1") (pintype "input"))
      (node (ref "IC1") (pin "A11") (pinfunction "GND_A11") (pintype "input"))
      (node (ref "IC1") (pin "B8") (pinfunction "GND_B8") (pintype "input"))
      (node (ref "IC1") (pin "C15") (pinfunction "GND_C15") (pintype "input"))
      (node (ref "IC1") (pin "C5") (pinfunction "GND_C5") (pintype "input"))
      (node (ref "IC1") (pin "D12") (pinfunction "GND_D12") (pintype "input"))
      (node (ref "IC1") (pin "D2") (pinfunction "GND_D2") (pintype "input"))
      (node (ref "IC1") (pin "E9") (pinfunction "GND_E9") (pintype "input"))
      (node (ref "IC1") (pin "F10") (pinfunction "GND_F10") (pintype "input"))
      (node (ref "IC1") (pin "F16") (pinfunction "GND_F16") (pintype "input"))
      (node (ref "IC1") (pin "F6") (pinfunction "GND_F6") (pintype "input"))
      (node (ref "IC1") (pin "F8") (pinfunction "VCCBAT_F8") (pintype "input"))
      (node (ref "IC1") (pin "G13") (pinfunction "GND_G13") (pintype "input"))
      (node (ref "IC1") (pin "G3") (pinfunction "GND_G3") (pintype "input"))
      (node (ref "IC1") (pin "G7") (pinfunction "GNDADC_G7") (pintype "input"))
      (node (ref "IC1") (pin "G9") (pinfunction "GND_G9") (pintype "input"))
      (node (ref "IC1") (pin "H6") (pinfunction "GND_H6") (pintype "input"))
      (node (ref "IC1") (pin "H7") (pinfunction "VREFN_H7") (pintype "bidirectional"))
      (node (ref "IC1") (pin "H8") (pinfunction "VP_H8") (pintype "bidirectional"))
      (node (ref "IC1") (pin "J11") (pinfunction "GND_J11") (pintype "input"))
      (node (ref "IC1") (pin "J7") (pinfunction "VN_J7") (pintype "bidirectional"))
      (node (ref "IC1") (pin "J8") (pinfunction "VREFP_J8") (pintype "bidirectional"))
      (node (ref "IC1") (pin "J9") (pinfunction "GND_J9") (pintype "input"))
      (node (ref "IC1") (pin "K14") (pinfunction "GND_K14") (pintype "input"))
      (node (ref "IC1") (pin "K4") (pinfunction "GND_K4") (pintype "input"))
      (node (ref "IC1") (pin "K6") (pinfunction "GND_K6") (pintype "input"))
      (node (ref "IC1") (pin "K7") (pinfunction "DXN_K7") (pintype "bidirectional"))
      (node (ref "IC1") (pin "K8") (pinfunction "DXP_K8") (pintype "bidirectional"))
      (node (ref "IC1") (pin "L1") (pinfunction "GND_L1") (pintype "input"))
      (node (ref "IC1") (pin "L11") (pinfunction "GND_L11") (pintype "input"))
      (node (ref "IC1") (pin "M10") (pinfunction "M1_M10") (pintype "bidirectional"))
      (node (ref "IC1") (pin "M11") (pinfunction "M2_M11") (pintype "bidirectional"))
      (node (ref "IC1") (pin "M8") (pinfunction "GND_M8") (pintype "input"))
      (node (ref "IC1") (pin "N15") (pinfunction "GND_N15") (pintype "input"))
      (node (ref "IC1") (pin "N5") (pinfunction "GND_N5") (pintype "input"))
      (node (ref "IC1") (pin "P12") (pinfunction "GND_P12") (pintype "input"))
      (node (ref "IC1") (pin "P2") (pinfunction "GND_P2") (pintype "input"))
      (node (ref "IC1") (pin "R9") (pinfunction "GND_R9") (pintype "input"))
      (node (ref "IC1") (pin "T16") (pinfunction "GND_T16") (pintype "input"))
      (node (ref "IC1") (pin "T6") (pinfunction "GND_T6") (pintype "input"))
      (node (ref "IC2") (pin "2") (pinfunction "GND_2") (pintype "input"))
      (node (ref "IC3") (pin "2") (pinfunction "GND_2") (pintype "input"))
      (node (ref "IC4") (pin "10") (pinfunction "GND_10") (pintype "input"))
      (node (ref "IC5") (pin "10") (pinfunction "GND_10") (pintype "input"))
      (node (ref "IC6") (pin "4") (pinfunction "GND_4") (pintype "input"))
      (node (ref "IC7") (pin "2") (pinfunction "VSS_2") (pintype "input"))
      (node (ref "IC8") (pin "10") (pinfunction "TEST_10") (pintype "bidirectional"))
      (node (ref "IC8") (pin "21") (pinfunction "GND_21") (pintype "input"))
      (node (ref "IC8") (pin "41") (pinfunction "GND_41") (pintype "input"))
      (node (ref "IC8") (pin "45") (pinfunction "GND_45") (pintype "input"))
      (node (ref "IC8") (pin "HT") (pinfunction "HT_HT") (pintype "input"))
      (node (ref "IC9") (pin "B3") (pinfunction "VSS_B3") (pintype "input"))
      (node (ref "IC9") (pin "C1") (pinfunction "VSSQ_C1") (pintype "input"))
      (node (ref "IC9") (pin "E5") (pinfunction "VSSQ_E5") (pintype "input"))
      (node (ref "R10") (pin "1") (pinfunction "1_1") (pintype "passive"))
      (node (ref "R12") (pin "1") (pinfunction "1_1") (pintype "passive"))
      (node (ref "R13") (pin "1") (pinfunction "1_1") (pintype "passive"))
      (node (ref "R14") (pin "1") (pinfunction "1_1") (pintype "passive"))
      (node (ref "R18") (pin "1") (pinfunction "1_1") (pintype "passive"))
      (node (ref "R2") (pin "1") (pinfunction "1_1") (pintype "passive"))
      (node (ref "R20") (pin "2") (pinfunction "2_2") (pintype "passive"))
      (node (ref "R4") (pin "1") (pinfunction "1_1") (pintype "passive"))
      (node (ref "R6") (pin "1") (pinfunction "1_1") (pintype "passive"))
      (node (ref "R8") (pin "1") (pinfunction "1_1") (pintype "passive"))
      (node (ref "R9") (pin "1") (pinfunction "1_1") (pintype "passive"))
      (node (ref "TP5") (pin "1") (pinfunction "1_1") (pintype "passive"))
      (node (ref "X1") (pin "2") (pinfunction "GND_2") (pintype "input"))
      (node (ref "X2") (pin "2") (pinfunction "GND_2") (pintype "passive"))
      (node (ref "X2") (pin "4") (pinfunction "GND_4") (pintype "passive"))
    )
    (net (code "46") (name "INIT_B") (class "Default")
      (node (ref "IC1") (pin "K10") (pinfunction "INIT_B_K10") (pintype "bidirectional"))
      (node (ref "R15") (pin "1") (pinfunction "1_1") (pintype "passive"))
    )
    (net (code "47") (name "IO0_14") (class "Default")
      (node (ref "CON2") (pin "35") (pinfunction "35_35") (pintype "passive"))
      (node (ref "IC1") (pin "K12") (pinfunction "IO_0_14_K12") (pintype "bidirectional"))
    )
    (net (code "48") (name "IO2N_14") (class "Default")
      (node (ref "CON2") (pin "34") (pinfunction "34_34") (pintype "passive"))
      (node (ref "IC1") (pin "K16") (pinfunction "IO_L2N_T0_D03_14_K16") (pintype "bidirectional"))
    )
    (net (code "49") (name "IO2N_34") (class "Default")
      (node (ref "CON1") (pin "42") (pinfunction "42_42") (pintype "passive"))
      (node (ref "IC1") (pin "M1") (pinfunction "IO_L2N_T0_34_M1") (pintype "bidirectional"))
    )
    (net (code "50") (name "IO2N_35") (class "Default")
      (node (ref "CON1") (pin "9") (pinfunction "9_9") (pintype "passive"))
      (node (ref "IC1") (pin "B5") (pinfunction "IO_L2N_T0_AD12N_35_B5") (pintype "bidirectional"))
    )
    (net (code "51") (name "IO2P_14") (class "Default")
      (node (ref "CON2") (pin "36") (pinfunction "36_36") (pintype "passive"))
      (node (ref "IC1") (pin "K15") (pinfunction "IO_L2P_T0_D02_14_K15") (pintype "bidirectional"))
    )
    (net (code "52") (name "IO2P_34") (class "Default")
      (node (ref "CON1") (pin "44") (pinfunction "44_44") (pintype "passive"))
      (node (ref "IC1") (pin "M2") (pinfunction "IO_L2P_T0_34_M2") (pintype "bidirectional"))
    )
    (net (code "53") (name "IO2P_35") (class "Default")
      (node (ref "CON1") (pin "7") (pinfunction "7_7") (pintype "passive"))
      (node (ref "IC1") (pin "B6") (pinfunction "IO_L2P_T0_AD12P_35_B6") (pintype "bidirectional"))
    )
    (net (code "54") (name "IO3N_35") (class "Default")
      (node (ref "CON1") (pin "6") (pinfunction "6_6") (pintype "passive"))
      (node (ref "IC1") (pin "A4") (pinfunction "IO_L3N_T0_DQS_AD5N_35_A4") (pintype "bidirectional"))
    )
    (net (code "55") (name "IO3P_35") (class "Default")
      (node (ref "CON1") (pin "4") (pinfunction "4_4") (pintype "passive"))
      (node (ref "IC1") (pin "A5") (pinfunction "IO_L3P_T0_DQS_AD5P_35_A5") (pintype "bidirectional"))
    )
    (net (code "56") (name "IO4N_14") (class "Default")
      (node (ref "CON2") (pin "30") (pinfunction "30_30") (pintype "passive"))
      (node (ref "IC1") (pin "M14") (pinfunction "IO_L4N_T0_D05_14_M14") (pintype "bidirectional"))
    )
    (net (code "57") (name "IO4N_34") (class "Default")
      (node (ref "CON1") (pin "48") (pinfunction "48_48") (pintype "passive"))
      (node (ref "IC1") (pin "P1") (pinfunction "IO_L4N_T0_34_P1") (pintype "bidirectional"))
    )
    (net (code "58") (name "IO4N_35") (class "Default")
      (node (ref "CON1") (pin "11") (pinfunction "11_11") (pintype "passive"))
      (node (ref "IC1") (pin "A3") (pinfunction "IO_L4N_T0_35_A3") (pintype "bidirectional"))
    )
    (net (code "59") (name "IO4P_14") (class "Default")
      (node (ref "CON2") (pin "32") (pinfunction "32_32") (pintype "passive"))
      (node (ref "IC1") (pin "L14") (pinfunction "IO_L4P_T0_D04_14_L14") (pintype "bidirectional"))
    )
    (net (code "60") (name "IO4P_34") (class "Default")
      (node (ref "CON1") (pin "46") (pinfunction "46_46") (pintype "passive"))
      (node (ref "IC1") (pin "N1") (pinfunction "IO_L4P_T0_34_N1") (pintype "bidirectional"))
    )
    (net (code "61") (name "IO4P_35") (class "Default")
      (node (ref "CON1") (pin "13") (pinfunction "13_13") (pintype "passive"))
      (node (ref "IC1") (pin "B4") (pinfunction "IO_L4P_T0_35_B4") (pintype "bidirectional"))
    )
    (net (code "62") (name "IO5N_34") (class "Default")
      (node (ref "CON1") (pin "43") (pinfunction "43_43") (pintype "passive"))
      (node (ref "IC1") (pin "P3") (pinfunction "IO_L5N_T0_34_P3") (pintype "bidirectional"))
    )
    (net (code "63") (name "IO5N_35") (class "Default")
      (node (ref "CON1") (pin "5") (pinfunction "5_5") (pintype "passive"))
      (node (ref "IC1") (pin "C6") (pinfunction "IO_L5N_T0_AD13N_35_C6") (pintype "bidirectional"))
    )
    (net (code "64") (name "IO5P_14") (class "Default")
      (node (ref "CON2") (pin "33") (pinfunction "33_33") (pintype "passive"))
      (node (ref "IC1") (pin "K13") (pinfunction "IO_L5P_T0_D06_14_K13") (pintype "bidirectional"))
    )
    (net (code "65") (name "IO5P_34") (class "Default")
      (node (ref "CON1") (pin "41") (pinfunction "41_41") (pintype "passive"))
      (node (ref "IC1") (pin "P4") (pinfunction "IO_L5P_T0_34_P4") (pintype "bidirectional"))
    )
    (net (code "66") (name "IO5P_35") (class "Default")
      (node (ref "CON1") (pin "3") (pinfunction "3_3") (pintype "passive"))
      (node (ref "IC1") (pin "C7") (pinfunction "IO_L5P_T0_AD13P_35_C7") (pintype "bidirectional"))
    )
    (net (code "67") (name "IO7N_14") (class "Default")
      (node (ref "CON2") (pin "26") (pinfunction "26_26") (pintype "passive"))
      (node (ref "IC1") (pin "N16") (pinfunction "IO_L7N_T1_D10_14_N16") (pintype "bidirectional"))
    )
    (net (code "68") (name "IO7N_34") (class "Default")
      (node (ref "CON1") (pin "50") (pinfunction "50_50") (pintype "passive"))
      (node (ref "IC1") (pin "R1") (pinfunction "IO_L7N_T1_34_R1") (pintype "bidirectional"))
    )
    (net (code "69") (name "IO7N_35") (class "Default")
      (node (ref "CON1") (pin "15") (pinfunction "15_15") (pintype "passive"))
      (node (ref "IC1") (pin "C2") (pinfunction "IO_L7N_T1_AD6N_35_C2") (pintype "bidirectional"))
    )
    (net (code "70") (name "IO7P_14") (class "Default")
      (node (ref "CON2") (pin "28") (pinfunction "28_28") (pintype "passive"))
      (node (ref "IC1") (pin "M16") (pinfunction "IO_L7P_T1_D09_14_M16") (pintype "bidirectional"))
    )
    (net (code "71") (name "IO7P_34") (class "Default")
      (node (ref "CON1") (pin "52") (pinfunction "52_52") (pintype "passive"))
      (node (ref "IC1") (pin "R2") (pinfunction "IO_L7P_T1_34_R2") (pintype "bidirectional"))
    )
    (net (code "72") (name "IO7P_35") (class "Default")
      (node (ref "CON1") (pin "17") (pinfunction "17_17") (pintype "passive"))
      (node (ref "IC1") (pin "C3") (pinfunction "IO_L7P_T1_AD6P_35_C3") (pintype "bidirectional"))
    )
    (net (code "73") (name "IO8N_14") (class "Default")
      (node (ref "CON2") (pin "22") (pinfunction "22_22") (pintype "passive"))
      (node (ref "IC1") (pin "P16") (pinfunction "IO_L8N_T1_D12_14_P16") (pintype "bidirectional"))
    )
    (net (code "74") (name "IO8N_15") (class "Default")
      (node (ref "CON2") (pin "57") (pinfunction "57_57") (pintype "passive"))
      (node (ref "IC1") (pin "B14") (pinfunction "IO_L8N_T1_AD10N_15_B14") (pintype "bidirectional"))
    )
    (net (code "75") (name "IO8N_34") (class "Default")
      (node (ref "CON1") (pin "47") (pinfunction "47_47") (pintype "passive"))
      (node (ref "IC1") (pin "T2") (pinfunction "IO_L8N_T1_34_T2") (pintype "bidirectional"))
    )
    (net (code "76") (name "IO8N_35") (class "Default")
      (node (ref "CON1") (pin "8") (pinfunction "8_8") (pintype "passive"))
      (node (ref "IC1") (pin "A2") (pinfunction "IO_L8N_T1_AD14N_35_A2") (pintype "bidirectional"))
    )
    (net (code "77") (name "IO8P_14") (class "Default")
      (node (ref "CON2") (pin "24") (pinfunction "24_24") (pintype "passive"))
      (node (ref "IC1") (pin "P15") (pinfunction "IO_L8P_T1_D11_14_P15") (pintype "bidirectional"))
    )
    (net (code "78") (name "IO8P_15") (class "Default")
      (node (ref "CON2") (pin "55") (pinfunction "55_55") (pintype "passive"))
      (node (ref "IC1") (pin "C14") (pinfunction "IO_L8P_T1_AD10P_15_C14") (pintype "bidirectional"))
    )
    (net (code "79") (name "IO8P_34") (class "Default")
      (node (ref "CON1") (pin "45") (pinfunction "45_45") (pintype "passive"))
      (node (ref "IC1") (pin "R3") (pinfunction "IO_L8P_T1_34_R3") (pintype "bidirectional"))
    )
    (net (code "80") (name "IO8P_35") (class "Default")
      (node (ref "CON1") (pin "10") (pinfunction "10_10") (pintype "passive"))
      (node (ref "IC1") (pin "B2") (pinfunction "IO_L8P_T1_AD14P_35_B2") (pintype "bidirectional"))
    )
    (net (code "81") (name "IO9N_14") (class "Default")
      (node (ref "CON2") (pin "25") (pinfunction "25_25") (pintype "passive"))
      (node (ref "IC1") (pin "R16") (pinfunction "IO_L9N_T1_DQS_D13_14_R16") (pintype "bidirectional"))
    )
    (net (code "82") (name "IO9N_15") (class "Default")
      (node (ref "CON2") (pin "58") (pinfunction "58_58") (pintype "passive"))
      (node (ref "IC1") (pin "A15") (pinfunction "IO_L9N_T1_DQS_AD3N_15_A15") (pintype "bidirectional"))
    )
    (net (code "83") (name "IO9N_34") (class "Default")
      (node (ref "CON1") (pin "49") (pinfunction "49_49") (pintype "passive"))
      (node (ref "IC1") (pin "T3") (pinfunction "IO_L9N_T1_DQS_34_T3") (pintype "bidirectional"))
    )
    (net (code "84") (name "IO9N_35") (class "Default")
      (node (ref "CON1") (pin "12") (pinfunction "12_12") (pintype "passive"))
      (node (ref "IC1") (pin "B1") (pinfunction "IO_L9N_T1_DQS_AD7N_35_B1") (pintype "bidirectional"))
    )
    (net (code "85") (name "IO9P_14") (class "Default")
      (node (ref "CON2") (pin "27") (pinfunction "27_27") (pintype "passive"))
      (node (ref "IC1") (pin "R15") (pinfunction "IO_L9P_T1_DQS_14_R15") (pintype "bidirectional"))
    )
    (net (code "86") (name "IO9P_15") (class "Default")
      (node (ref "CON2") (pin "56") (pinfunction "56_56") (pintype "passive"))
      (node (ref "IC1") (pin "B15") (pinfunction "IO_L9P_T1_DQS_AD3P_15_B15") (pintype "bidirectional"))
    )
    (net (code "87") (name "IO9P_34") (class "Default")
      (node (ref "CON1") (pin "51") (pinfunction "51_51") (pintype "passive"))
      (node (ref "IC1") (pin "T4") (pinfunction "IO_L9P_T1_DQS_34_T4") (pintype "bidirectional"))
    )
    (net (code "88") (name "IO9P_35") (class "Default")
      (node (ref "CON1") (pin "14") (pinfunction "14_14") (pintype "passive"))
      (node (ref "IC1") (pin "C1") (pinfunction "IO_L9P_T1_DQS_AD7P_35_C1") (pintype "bidirectional"))
    )
    (net (code "89") (name "IO10N_15") (class "Default")
      (node (ref "CON2") (pin "54") (pinfunction "54_54") (pintype "passive"))
      (node (ref "IC1") (pin "B16") (pinfunction "IO_L10N_T1_AD11N_15_B16") (pintype "bidirectional"))
    )
    (net (code "90") (name "IO10N_35") (class "Default")
      (node (ref "CON1") (pin "16") (pinfunction "16_16") (pintype "passive"))
      (node (ref "IC1") (pin "D1") (pinfunction "IO_L10N_T1_AD15N_35_D1") (pintype "bidirectional"))
    )
    (net (code "91") (name "IO10P_15") (class "Default")
      (node (ref "CON2") (pin "52") (pinfunction "52_52") (pintype "passive"))
      (node (ref "IC1") (pin "C16") (pinfunction "IO_L10P_T1_AD11P_15_C16") (pintype "bidirectional"))
    )
    (net (code "92") (name "IO10P_35") (class "Default")
      (node (ref "CON1") (pin "18") (pinfunction "18_18") (pintype "passive"))
      (node (ref "IC1") (pin "E2") (pinfunction "IO_L10P_T1_AD15P_35_E2") (pintype "bidirectional"))
    )
    (net (code "93") (name "IO11N_14") (class "Default")
      (node (ref "CON2") (pin "21") (pinfunction "21_21") (pintype "passive"))
      (node (ref "IC1") (pin "P13") (pinfunction "IO_L11N_T1_SRCC_14_P13") (pintype "bidirectional"))
    )
    (net (code "94") (name "IO11P_14") (class "Default")
      (node (ref "CON2") (pin "23") (pinfunction "23_23") (pintype "passive"))
      (node (ref "IC1") (pin "N13") (pinfunction "IO_L11P_T1_SRCC_14_N13") (pintype "bidirectional"))
    )
    (net (code "95") (name "IO12N_14") (class "Default")
      (node (ref "CON2") (pin "29") (pinfunction "29_29") (pintype "passive"))
      (node (ref "IC1") (pin "P14") (pinfunction "IO_L12N_T1_MRCC_14_P14") (pintype "bidirectional"))
    )
    (net (code "96") (name "IO12N_35") (class "Default")
      (node (ref "CON1") (pin "19") (pinfunction "19_19") (pintype "passive"))
      (node (ref "IC1") (pin "C4") (pinfunction "IO_L12N_T1_MRCC_35_C4") (pintype "bidirectional"))
    )
    (net (code "97") (name "IO12P_14") (class "Default")
      (node (ref "CON2") (pin "31") (pinfunction "31_31") (pintype "passive"))
      (node (ref "IC1") (pin "N14") (pinfunction "IO_L12P_T1_MRCC_14_N14") (pintype "bidirectional"))
    )
    (net (code "98") (name "IO12P_35") (class "Default")
      (node (ref "CON1") (pin "21") (pinfunction "21_21") (pintype "passive"))
      (node (ref "IC1") (pin "D4") (pinfunction "IO_L12P_T1_MRCC_35_D4") (pintype "bidirectional"))
    )
    (net (code "99") (name "IO13N_15") (class "Default")
      (node (ref "CON2") (pin "49") (pinfunction "49_49") (pintype "passive"))
      (node (ref "IC1") (pin "E13") (pinfunction "IO_L13N_T2_MRCC_15_E13") (pintype "bidirectional"))
    )
    (net (code "100") (name "IO13P_15") (class "Default")
      (node (ref "CON2") (pin "47") (pinfunction "47_47") (pintype "passive"))
      (node (ref "IC1") (pin "E12") (pinfunction "IO_L13P_T2_MRCC_15_E12") (pintype "bidirectional"))
    )
    (net (code "101") (name "IO14N_35") (class "Default")
      (node (ref "CON1") (pin "23") (pinfunction "23_23") (pintype "passive"))
      (node (ref "IC1") (pin "F3") (pinfunction "IO_L14N_T2_SRCC_35_F3") (pintype "bidirectional"))
    )
    (net (code "102") (name "IO14P_35") (class "Default")
      (node (ref "CON1") (pin "25") (pinfunction "25_25") (pintype "passive"))
      (node (ref "IC1") (pin "F4") (pinfunction "IO_L14P_T2_SRCC_35_F4") (pintype "bidirectional"))
    )
    (net (code "103") (name "IO15N_15") (class "Default")
      (node (ref "CON2") (pin "51") (pinfunction "51_51") (pintype "passive"))
      (node (ref "IC1") (pin "D15") (pinfunction "IO_L15N_T2_DQS_ADV_B_15_D15") (pintype "bidirectional"))
    )
    (net (code "104") (name "IO15N_35") (class "Default")
      (node (ref "CON1") (pin "20") (pinfunction "20_20") (pintype "passive"))
      (node (ref "IC1") (pin "E1") (pinfunction "IO_L15N_T2_DQS_35_E1") (pintype "bidirectional"))
    )
    (net (code "105") (name "IO15P_15") (class "Default")
      (node (ref "CON2") (pin "53") (pinfunction "53_53") (pintype "passive"))
      (node (ref "IC1") (pin "D14") (pinfunction "IO_L15P_T2_DQS_15_D14") (pintype "bidirectional"))
    )
    (net (code "106") (name "IO15P_35") (class "Default")
      (node (ref "CON1") (pin "22") (pinfunction "22_22") (pintype "passive"))
      (node (ref "IC1") (pin "F2") (pinfunction "IO_L15P_T2_DQS_35_F2") (pintype "bidirectional"))
    )
    (net (code "107") (name "IO17N_15") (class "Default")
      (node (ref "CON2") (pin "50") (pinfunction "50_50") (pintype "passive"))
      (node (ref "IC1") (pin "D16") (pinfunction "IO_L17N_T2_A25_15_D16") (pintype "bidirectional"))
    )
    (net (code "108") (name "IO17N_35") (class "Default")
      (node (ref "CON1") (pin "24") (pinfunction "24_24") (pintype "passive"))
      (node (ref "IC1") (pin "G1") (pinfunction "IO_L17N_T2_35_G1") (pintype "bidirectional"))
    )
    (net (code "109") (name "IO17P_15") (class "Default")
      (node (ref "CON2") (pin "48") (pinfunction "48_48") (pintype "passive"))
      (node (ref "IC1") (pin "E16") (pinfunction "IO_L17P_T2_A26_15_E16") (pintype "bidirectional"))
    )
    (net (code "110") (name "IO17P_35") (class "Default")
      (node (ref "CON1") (pin "26") (pinfunction "26_26") (pintype "passive"))
      (node (ref "IC1") (pin "G2") (pinfunction "IO_L17P_T2_35_G2") (pintype "bidirectional"))
    )
    (net (code "111") (name "IO19N_35") (class "Default")
      (node (ref "CON1") (pin "35") (pinfunction "35_35") (pintype "passive"))
      (node (ref "IC1") (pin "J4") (pinfunction "IO_L19N_T3_VREF_35_J4") (pintype "bidirectional"))
    )
    (net (code "112") (name "IO19P_35") (class "Default")
      (node (ref "CON1") (pin "37") (pinfunction "37_37") (pintype "passive"))
      (node (ref "IC1") (pin "J5") (pinfunction "IO_L19P_T3_35_J5") (pintype "bidirectional"))
    )
    (net (code "113") (name "IO20N_35") (class "Default")
      (node (ref "CON1") (pin "28") (pinfunction "28_28") (pintype "passive"))
      (node (ref "IC1") (pin "H1") (pinfunction "IO_L20N_T3_35_H1") (pintype "bidirectional"))
    )
    (net (code "114") (name "IO20P_35") (class "Default")
      (node (ref "CON1") (pin "30") (pinfunction "30_30") (pintype "passive"))
      (node (ref "IC1") (pin "H2") (pinfunction "IO_L20P_T3_35_H2") (pintype "bidirectional"))
    )
    (net (code "115") (name "IO21N_15") (class "Default")
      (node (ref "CON2") (pin "45") (pinfunction "45_45") (pintype "passive"))
      (node (ref "IC1") (pin "F14") (pinfunction "IO_L21N_T3_DQS_A18_15_F14") (pintype "bidirectional"))
    )
    (net (code "116") (name "IO21N_35") (class "Default")
      (node (ref "CON1") (pin "27") (pinfunction "27_27") (pintype "passive"))
      (node (ref "IC1") (pin "H3") (pinfunction "IO_L21N_T3_DQS_35_H3") (pintype "bidirectional"))
    )
    (net (code "117") (name "IO21P_15") (class "Default")
      (node (ref "CON2") (pin "43") (pinfunction "43_43") (pintype "passive"))
      (node (ref "IC1") (pin "G14") (pinfunction "IO_L21P_T3_DQS_15_G14") (pintype "bidirectional"))
    )
    (net (code "118") (name "IO21P_35") (class "Default")
      (node (ref "CON1") (pin "29") (pinfunction "29_29") (pintype "passive"))
      (node (ref "IC1") (pin "J3") (pinfunction "IO_L21P_T3_DQS_35_J3") (pintype "bidirectional"))
    )
    (net (code "119") (name "IO22N_15") (class "Default")
      (node (ref "CON2") (pin "46") (pinfunction "46_46") (pintype "passive"))
      (node (ref "IC1") (pin "G16") (pinfunction "IO_L22N_T3_A16_15_G16") (pintype "bidirectional"))
    )
    (net (code "120") (name "IO22N_35") (class "Default")
      (node (ref "CON1") (pin "32") (pinfunction "32_32") (pintype "passive"))
      (node (ref "IC1") (pin "J1") (pinfunction "IO_L22N_T3_35_J1") (pintype "bidirectional"))
    )
    (net (code "121") (name "IO22P_15") (class "Default")
      (node (ref "CON2") (pin "44") (pinfunction "44_44") (pintype "passive"))
      (node (ref "IC1") (pin "H16") (pinfunction "IO_L22P_T3_A17_15_H16") (pintype "bidirectional"))
    )
    (net (code "122") (name "IO22P_35") (class "Default")
      (node (ref "CON1") (pin "34") (pinfunction "34_34") (pintype "passive"))
      (node (ref "IC1") (pin "K1") (pinfunction "IO_L22P_T3_35_K1") (pintype "bidirectional"))
    )
    (net (code "123") (name "IO23N_15") (class "Default")
      (node (ref "CON2") (pin "40") (pinfunction "40_40") (pintype "passive"))
      (node (ref "IC1") (pin "J16") (pinfunction "IO_L23N_T3_FWE_B_15_J16") (pintype "bidirectional"))
    )
    (net (code "124") (name "IO23N_35") (class "Default")
      (node (ref "CON1") (pin "38") (pinfunction "38_38") (pintype "passive"))
      (node (ref "IC1") (pin "L2") (pinfunction "IO_L23N_T3_35_L2") (pintype "bidirectional"))
    )
    (net (code "125") (name "IO23P_15") (class "Default")
      (node (ref "CON2") (pin "42") (pinfunction "42_42") (pintype "passive"))
      (node (ref "IC1") (pin "J15") (pinfunction "IO_L23P_T3_FOE_B_15_J15") (pintype "bidirectional"))
    )
    (net (code "126") (name "IO23P_35") (class "Default")
      (node (ref "CON1") (pin "36") (pinfunction "36_36") (pintype "passive"))
      (node (ref "IC1") (pin "L3") (pinfunction "IO_L23P_T3_35_L3") (pintype "bidirectional"))
    )
    (net (code "127") (name "IO24N_15") (class "Default")
      (node (ref "CON2") (pin "41") (pinfunction "41_41") (pintype "passive"))
      (node (ref "IC1") (pin "G15") (pinfunction "IO_L24N_T3_RS0_15_G15") (pintype "bidirectional"))
    )
    (net (code "128") (name "IO24N_35") (class "Default")
      (node (ref "CON1") (pin "31") (pinfunction "31_31") (pintype "passive"))
      (node (ref "IC1") (pin "K2") (pinfunction "IO_L24N_T3_35_K2") (pintype "bidirectional"))
    )
    (net (code "129") (name "IO24P_15") (class "Default")
      (node (ref "CON2") (pin "39") (pinfunction "39_39") (pintype "passive"))
      (node (ref "IC1") (pin "H14") (pinfunction "IO_L24P_T3_RS1_15_H14") (pintype "bidirectional"))
    )
    (net (code "130") (name "IO24P_35") (class "Default")
      (node (ref "CON1") (pin "33") (pinfunction "33_33") (pintype "passive"))
      (node (ref "IC1") (pin "K3") (pinfunction "IO_L24P_T3_35_K3") (pintype "bidirectional"))
    )
    (net (code "131") (name "JTAG_TCK") (class "Default")
      (node (ref "IC1") (pin "L7") (pinfunction "TCK_L7") (pintype "bidirectional"))
      (node (ref "IC8") (pin "32") (pinfunction "BDBUS0_32") (pintype "bidirectional"))
      (node (ref "R6") (pin "2") (pinfunction "2_2") (pintype "passive"))
      (node (ref "TP3") (pin "1") (pinfunction "1_1") (pintype "passive"))
    )
    (net (code "132") (name "JTAG_TDI") (class "Default")
      (node (ref "IC1") (pin "N7") (pinfunction "TDI_N7") (pintype "bidirectional"))
      (node (ref "IC8") (pin "33") (pinfunction "BDBUS1_33") (pintype "bidirectional"))
      (node (ref "R5") (pin "1") (pinfunction "1_1") (pintype "passive"))
      (node (ref "TP2") (pin "1") (pinfunction "1_1") (pintype "passive"))
    )
    (net (code "133") (name "JTAG_TDO") (class "Default")
      (node (ref "IC1") (pin "N8") (pinfunction "TDO_N8") (pintype "bidirectional"))
      (node (ref "IC8") (pin "34") (pinfunction "BDBUS2_34") (pintype "bidirectional"))
      (node (ref "TP4") (pin "1") (pinfunction "1_1") (pintype "passive"))
    )
    (net (code "134") (name "JTAG_TMS") (class "Default")
      (node (ref "IC1") (pin "M7") (pinfunction "TMS_M7") (pintype "bidirectional"))
      (node (ref "IC8") (pin "35") (pinfunction "BDBUS3_35") (pintype "bidirectional"))
      (node (ref "R7") (pin "1") (pinfunction "1_1") (pintype "passive"))
      (node (ref "TP1") (pin "1") (pinfunction "1_1") (pintype "passive"))
    )
    (net (code "135") (name "LED0") (class "Default")
      (node (ref "D1") (pin "A") (pinfunction "A_A") (pintype "passive"))
      (node (ref "IC1") (pin "R7") (pinfunction "IO_L24N_T3_A00_D16_14_R7") (pintype "bidirectional"))
    )
    (net (code "136") (name "LED1") (class "Default")
      (node (ref "D2") (pin "A") (pinfunction "A_A") (pintype "passive"))
      (node (ref "IC1") (pin "R6") (pinfunction "IO_L24P_T3_A01_D17_14_R6") (pintype "bidirectional"))
    )
    (net (code "137") (name "LED2") (class "Default")
      (node (ref "D3") (pin "A") (pinfunction "A_A") (pintype "passive"))
      (node (ref "IC1") (pin "T5") (pinfunction "IO_L23N_T3_A02_D18_14_T5") (pintype "bidirectional"))
    )
    (net (code "138") (name "LED3") (class "Default")
      (node (ref "D4") (pin "A") (pinfunction "A_A") (pintype "passive"))
      (node (ref "IC1") (pin "R5") (pinfunction "IO_L23P_T3_A03_D19_14_R5") (pintype "bidirectional"))
    )
    (net (code "139") (name "Net-(C23-Pad1)") (class "Default")
      (node (ref "C23") (pin "1") (pinfunction "1_1") (pintype "passive"))
      (node (ref "FB5") (pin "1") (pinfunction "1_1") (pintype "passive"))
      (node (ref "IC4") (pin "6") (pinfunction "OUT_6") (pintype "output"))
      (node (ref "IC4") (pin "7") (pinfunction "OUT_7") (pintype "output"))
      (node (ref "IC4") (pin "8") (pinfunction "OUT_8") (pintype "output"))
      (node (ref "R1") (pin "2") (pinfunction "2_2") (pintype "passive"))
    )
    (net (code "140") (name "Net-(C24-Pad1)") (class "Default")
      (node (ref "C24") (pin "1") (pinfunction "1_1") (pintype "passive"))
      (node (ref "FB6") (pin "1") (pinfunction "1_1") (pintype "passive"))
      (node (ref "IC5") (pin "6") (pinfunction "OUT_6") (pintype "output"))
      (node (ref "IC5") (pin "7") (pinfunction "OUT_7") (pintype "output"))
      (node (ref "IC5") (pin "8") (pinfunction "OUT_8") (pintype "output"))
      (node (ref "R3") (pin "2") (pinfunction "2_2") (pintype "passive"))
    )
    (net (code "141") (name "Net-(CON3-CC1)") (class "Default")
      (node (ref "CON3") (pin "A5:CC1") (pinfunction "CC1_A5:CC1") (pintype "bidirectional"))
      (node (ref "R12") (pin "2") (pinfunction "2_2") (pintype "passive"))
    )
    (net (code "142") (name "Net-(CON3-CC2)") (class "Default")
      (node (ref "CON3") (pin "B5:CC2") (pinfunction "CC2_B5:CC2") (pintype "bidirectional"))
      (node (ref "R13") (pin "2") (pinfunction "2_2") (pintype "passive"))
    )
    (net (code "143") (name "Net-(D1-PadK)") (class "Default")
      (node (ref "D1") (pin "K") (pinfunction "K_K") (pintype "passive"))
      (node (ref "R8") (pin "2") (pinfunction "2_2") (pintype "passive"))
    )
    (net (code "144") (name "Net-(D2-PadK)") (class "Default")
      (node (ref "D2") (pin "K") (pinfunction "K_K") (pintype "passive"))
      (node (ref "R9") (pin "2") (pinfunction "2_2") (pintype "passive"))
    )
    (net (code "145") (name "Net-(D3-PadK)") (class "Default")
      (node (ref "D3") (pin "K") (pinfunction "K_K") (pintype "passive"))
      (node (ref "R10") (pin "2") (pinfunction "2_2") (pintype "passive"))
    )
    (net (code "146") (name "Net-(D4-PadK)") (class "Default")
      (node (ref "D4") (pin "K") (pinfunction "K_K") (pintype "passive"))
      (node (ref "R14") (pin "2") (pinfunction "2_2") (pintype "passive"))
    )
    (net (code "147") (name "Net-(D5-PadK)") (class "Default")
      (node (ref "D5") (pin "K") (pinfunction "K_K") (pintype "passive"))
      (node (ref "R18") (pin "2") (pinfunction "2_2") (pintype "passive"))
    )
    (net (code "148") (name "Net-(IC2-OUT)") (class "Default")
      (node (ref "C21") (pin "1") (pinfunction "1_1") (pintype "passive"))
      (node (ref "FB3") (pin "1") (pinfunction "1_1") (pintype "passive"))
      (node (ref "IC2") (pin "5") (pinfunction "OUT_5") (pintype "output"))
    )
    (net (code "149") (name "Net-(IC3-OUT)") (class "Default")
      (node (ref "C22") (pin "1") (pinfunction "1_1") (pintype "passive"))
      (node (ref "FB4") (pin "1") (pinfunction "1_1") (pintype "passive"))
      (node (ref "IC3") (pin "5") (pinfunction "OUT_5") (pintype "output"))
    )
    (net (code "150") (name "Net-(IC4-FB)") (class "Default")
      (node (ref "IC4") (pin "9") (pinfunction "FB_9") (pintype "input"))
      (node (ref "R1") (pin "1") (pinfunction "1_1") (pintype "passive"))
      (node (ref "R2") (pin "2") (pinfunction "2_2") (pintype "passive"))
    )
    (net (code "151") (name "Net-(IC4-SW-Pad2)") (class "Default")
      (node (ref "IC4") (pin "2") (pinfunction "SW_2") (pintype "passive"))
      (node (ref "IC4") (pin "3") (pinfunction "SW_3") (pintype "passive"))
      (node (ref "IC4") (pin "4") (pinfunction "SW_4") (pintype "passive"))
    )
    (net (code "152") (name "Net-(IC5-FB)") (class "Default")
      (node (ref "IC5") (pin "9") (pinfunction "FB_9") (pintype "input"))
      (node (ref "R3") (pin "1") (pinfunction "1_1") (pintype "passive"))
      (node (ref "R4") (pin "2") (pinfunction "2_2") (pintype "passive"))
    )
    (net (code "153") (name "Net-(IC5-SW-Pad2)") (class "Default")
      (node (ref "IC5") (pin "2") (pinfunction "SW_2") (pintype "passive"))
      (node (ref "IC5") (pin "3") (pinfunction "SW_3") (pintype "passive"))
      (node (ref "IC5") (pin "4") (pinfunction "SW_4") (pintype "passive"))
    )
    (net (code "154") (name "Net-(IC7-CLK)") (class "Default")
      (node (ref "IC7") (pin "4") (pinfunction "CLK_4") (pintype "bidirectional"))
      (node (ref "IC8") (pin "56") (pinfunction "EECLK_56") (pintype "bidirectional"))
    )
    (net (code "155") (name "Net-(IC7-CS)") (class "Default")
      (node (ref "IC7") (pin "5") (pinfunction "CS_5") (pintype "bidirectional"))
      (node (ref "IC8") (pin "1") (pinfunction "EECS_1") (pintype "bidirectional"))
    )
    (net (code "156") (name "Net-(IC7-DI)") (class "Default")
      (node (ref "IC7") (pin "3") (pinfunction "DI_3") (pintype "bidirectional"))
      (node (ref "IC8") (pin "55") (pinfunction "EEDATA_55") (pintype "bidirectional"))
      (node (ref "R16") (pin "2") (pinfunction "2_2") (pintype "passive"))
    )
    (net (code "157") (name "Net-(IC7-DO)") (class "Default")
      (node (ref "IC7") (pin "1") (pinfunction "DO_1") (pintype "bidirectional"))
      (node (ref "R11") (pin "2") (pinfunction "2_2") (pintype "passive"))
      (node (ref "R16") (pin "1") (pinfunction "1_1") (pintype "passive"))
    )
    (net (code "158") (name "Net-(IC8-OSCI)") (class "Default")
      (node (ref "C55") (pin "1") (pinfunction "1_1") (pintype "passive"))
      (node (ref "IC8") (pin "3") (pinfunction "OSCI_3") (pintype "bidirectional"))
      (node (ref "X2") (pin "1") (pinfunction "1_1") (pintype "passive"))
    )
    (net (code "159") (name "Net-(IC8-OSCO)") (class "Default")
      (node (ref "C56") (pin "1") (pinfunction "1_1") (pintype "passive"))
      (node (ref "IC8") (pin "4") (pinfunction "OSCO_4") (pintype "bidirectional"))
      (node (ref "X2") (pin "3") (pinfunction "2_3") (pintype "passive"))
    )
    (net (code "160") (name "Net-(IC8-REF)") (class "Default")
      (node (ref "IC8") (pin "6") (pinfunction "REF_6") (pintype "bidirectional"))
      (node (ref "R20") (pin "1") (pinfunction "1_1") (pintype "passive"))
    )
    (net (code "161") (name "Net-(IC8-RESET#)") (class "Default")
      (node (ref "IC8") (pin "11") (pinfunction "RESET#_11") (pintype "bidirectional"))
      (node (ref "R21") (pin "2") (pinfunction "2_2") (pintype "passive"))
    )
    (net (code "162") (name "Net-(X1-OUT)") (class "Default")
      (node (ref "J3") (pin "1") (pinfunction "1_1") (pintype "passive"))
      (node (ref "X1") (pin "3") (pinfunction "OUT_3") (pintype "output"))
    )
    (net (code "163") (name "PROGRAM_B") (class "Default")
      (node (ref "IC1") (pin "L9") (pinfunction "PROGRAM_B_L9") (pintype "bidirectional"))
      (node (ref "R17") (pin "1") (pinfunction "1_1") (pintype "passive"))
    )
    (net (code "164") (name "USB_+5V") (class "Default")
      (node (ref "CON3") (pin "A4,B9:VBUS") (pinfunction "VBUS_A4,B9:VBUS") (pintype "output"))
      (node (ref "CON3") (pin "B4,A9:VBUS") (pinfunction "VBUS_B4,A9:VBUS") (pintype "output"))
      (node (ref "FB1") (pin "1") (pinfunction "1_1") (pintype "passive"))
    )
    (net (code "165") (name "VCCO34") (class "Default")
      (node (ref "C25") (pin "1") (pinfunction "1_1") (pintype "passive"))
      (node (ref "C29") (pin "1") (pinfunction "1_1") (pintype "passive"))
      (node (ref "C31") (pin "1") (pinfunction "1_1") (pintype "passive"))
      (node (ref "C35") (pin "1") (pinfunction "1_1") (pintype "passive"))
      (node (ref "IC1") (pin "M3") (pinfunction "VCCO_34_M3") (pintype "input"))
      (node (ref "IC1") (pin "R4") (pinfunction "VCCO_34_R4") (pintype "input"))
      (node (ref "IC1") (pin "T1") (pinfunction "VCCO_34_T1") (pintype "input"))
      (node (ref "J1") (pin "2") (pinfunction "2_2") (pintype "passive"))
    )
    (net (code "166") (name "VCCO35") (class "Default")
      (node (ref "C26") (pin "1") (pinfunction "1_1") (pintype "passive"))
      (node (ref "C30") (pin "1") (pinfunction "1_1") (pintype "passive"))
      (node (ref "C32") (pin "1") (pinfunction "1_1") (pintype "passive"))
      (node (ref "C36") (pin "1") (pinfunction "1_1") (pintype "passive"))
      (node (ref "IC1") (pin "A6") (pinfunction "VCCO_35_A6") (pintype "input"))
      (node (ref "IC1") (pin "B3") (pinfunction "VCCO_35_B3") (pintype "input"))
      (node (ref "IC1") (pin "D7") (pinfunction "VCCO_35_D7") (pintype "input"))
      (node (ref "IC1") (pin "E4") (pinfunction "VCCO_35_E4") (pintype "input"))
      (node (ref "IC1") (pin "F1") (pinfunction "VCCO_35_F1") (pintype "input"))
      (node (ref "IC1") (pin "J2") (pinfunction "VCCO_35_J2") (pintype "input"))
      (node (ref "J2") (pin "2") (pinfunction "2_2") (pintype "passive"))
    )
    (net (code "167") (name "VIN") (class "Default")
      (node (ref "C1") (pin "1") (pinfunction "1_1") (pintype "passive"))
      (node (ref "CON2") (pin "1") (pinfunction "1_1") (pintype "passive"))
      (node (ref "CON2") (pin "2") (pinfunction "2_2") (pintype "passive"))
      (node (ref "CON2") (pin "3") (pinfunction "3_3") (pintype "passive"))
      (node (ref "CON2") (pin "4") (pinfunction "4_4") (pintype "passive"))
      (node (ref "FB1") (pin "2") (pinfunction "2_2") (pintype "passive"))
      (node (ref "FB2") (pin "1") (pinfunction "1_1") (pintype "passive"))
    )
    (net (code "168") (name "unconnected-(IC1C-IO_25_14-PadP6)") (class "Default")
      (node (ref "IC1") (pin "P6") (pinfunction "IO_25_14_P6") (pintype "bidirectional"))
    )
    (net (code "169") (name "unconnected-(IC1C-IO_L3N_T0_DQS_EMCCLK_14-PadM15)") (class "Default")
      (node (ref "IC1") (pin "M15") (pinfunction "IO_L3N_T0_DQS_EMCCLK_14_M15") (pintype "bidirectional"))
    )
    (net (code "170") (name "unconnected-(IC1C-IO_L5N_T0_D07_14-PadL13)") (class "Default")
      (node (ref "IC1") (pin "L13") (pinfunction "IO_L5N_T0_D07_14_L13") (pintype "bidirectional"))
    )
    (net (code "171") (name "unconnected-(IC1C-IO_L6N_T0_D08_VREF_14-PadM12)") (class "Default")
      (node (ref "IC1") (pin "M12") (pinfunction "IO_L6N_T0_D08_VREF_14_M12") (pintype "bidirectional"))
    )
    (net (code "172") (name "unconnected-(IC1C-IO_L13N_T2_MRCC_14-PadN12)") (class "Default")
      (node (ref "IC1") (pin "N12") (pinfunction "IO_L13N_T2_MRCC_14_N12") (pintype "bidirectional"))
    )
    (net (code "173") (name "unconnected-(IC1C-IO_L14N_T2_SRCC_14-PadP11)") (class "Default")
      (node (ref "IC1") (pin "P11") (pinfunction "IO_L14N_T2_SRCC_14_P11") (pintype "bidirectional"))
    )
    (net (code "174") (name "unconnected-(IC1C-IO_L18N_T2_A11_D27_14-PadP9)") (class "Default")
      (node (ref "IC1") (pin "P9") (pinfunction "IO_L18N_T2_A11_D27_14_P9") (pintype "bidirectional"))
    )
    (net (code "175") (name "unconnected-(IC1C-IO_L18P_T2_A12_D28_14-PadN9)") (class "Default")
      (node (ref "IC1") (pin "N9") (pinfunction "IO_L18P_T2_A12_D28_14_N9") (pintype "bidirectional"))
    )
    (net (code "176") (name "unconnected-(IC1C-IO_L19N_T3_A09_D25_VREF_14-PadN6)") (class "Default")
      (node (ref "IC1") (pin "N6") (pinfunction "IO_L19N_T3_A09_D25_VREF_14_N6") (pintype "bidirectional"))
    )
    (net (code "177") (name "unconnected-(IC1C-IO_L19P_T3_A10_D26_14-PadM6)") (class "Default")
      (node (ref "IC1") (pin "M6") (pinfunction "IO_L19P_T3_A10_D26_14_M6") (pintype "bidirectional"))
    )
    (net (code "178") (name "unconnected-(IC1D-IO_0_15-PadD10)") (class "Default")
      (node (ref "IC1") (pin "D10") (pinfunction "IO_0_15_D10") (pintype "bidirectional"))
    )
    (net (code "179") (name "unconnected-(IC1D-IO_25_15-PadG11)") (class "Default")
      (node (ref "IC1") (pin "G11") (pinfunction "IO_25_15_G11") (pintype "bidirectional"))
    )
    (net (code "180") (name "unconnected-(IC1D-IO_L1N_T0_AD0N_15-PadC9)") (class "Default")
      (node (ref "IC1") (pin "C9") (pinfunction "IO_L1N_T0_AD0N_15_C9") (pintype "bidirectional"))
    )
    (net (code "181") (name "unconnected-(IC1D-IO_L3P_T0_DQS_AD1P_15-PadB9)") (class "Default")
      (node (ref "IC1") (pin "B9") (pinfunction "IO_L3P_T0_DQS_AD1P_15_B9") (pintype "bidirectional"))
    )
    (net (code "182") (name "unconnected-(IC1D-IO_L6N_T0_VREF_15-PadD9)") (class "Default")
      (node (ref "IC1") (pin "D9") (pinfunction "IO_L6N_T0_VREF_15_D9") (pintype "bidirectional"))
    )
    (net (code "183") (name "unconnected-(IC1D-IO_L11P_T1_SRCC_15-PadC11)") (class "Default")
      (node (ref "IC1") (pin "C11") (pinfunction "IO_L11P_T1_SRCC_15_C11") (pintype "bidirectional"))
    )
    (net (code "184") (name "unconnected-(IC1D-IO_L12P_T1_MRCC_15-PadD13)") (class "Default")
      (node (ref "IC1") (pin "D13") (pinfunction "IO_L12P_T1_MRCC_15_D13") (pintype "bidirectional"))
    )
    (net (code "185") (name "unconnected-(IC1D-IO_L14N_T2_SRCC_15-PadD11)") (class "Default")
      (node (ref "IC1") (pin "D11") (pinfunction "IO_L14N_T2_SRCC_15_D11") (pintype "bidirectional"))
    )
    (net (code "186") (name "unconnected-(IC1D-IO_L14P_T2_SRCC_15-PadE11)") (class "Default")
      (node (ref "IC1") (pin "E11") (pinfunction "IO_L14P_T2_SRCC_15_E11") (pintype "bidirectional"))
    )
    (net (code "187") (name "unconnected-(IC1D-IO_L16N_T2_A27_15-PadF13)") (class "Default")
      (node (ref "IC1") (pin "F13") (pinfunction "IO_L16N_T2_A27_15_F13") (pintype "bidirectional"))
    )
    (net (code "188") (name "unconnected-(IC1D-IO_L16P_T2_A28_15-PadF12)") (class "Default")
      (node (ref "IC1") (pin "F12") (pinfunction "IO_L16P_T2_A28_15_F12") (pintype "bidirectional"))
    )
    (net (code "189") (name "unconnected-(IC1D-IO_L18N_T2_A23_15-PadE15)") (class "Default")
      (node (ref "IC1") (pin "E15") (pinfunction "IO_L18N_T2_A23_15_E15") (pintype "bidirectional"))
    )
    (net (code "190") (name "unconnected-(IC1D-IO_L18P_T2_A24_15-PadF15)") (class "Default")
      (node (ref "IC1") (pin "F15") (pinfunction "IO_L18P_T2_A24_15_F15") (pintype "bidirectional"))
    )
    (net (code "191") (name "unconnected-(IC1D-IO_L19N_T3_A21_VREF_15-PadG12)") (class "Default")
      (node (ref "IC1") (pin "G12") (pinfunction "IO_L19N_T3_A21_VREF_15_G12") (pintype "bidirectional"))
    )
    (net (code "192") (name "unconnected-(IC1D-IO_L19P_T3_A22_15-PadH11)") (class "Default")
      (node (ref "IC1") (pin "H11") (pinfunction "IO_L19P_T3_A22_15_H11") (pintype "bidirectional"))
    )
    (net (code "193") (name "unconnected-(IC1D-IO_L20N_T3_A19_15-PadH13)") (class "Default")
      (node (ref "IC1") (pin "H13") (pinfunction "IO_L20N_T3_A19_15_H13") (pintype "bidirectional"))
    )
    (net (code "194") (name "unconnected-(IC1D-IO_L20P_T3_A20_15-PadH12)") (class "Default")
      (node (ref "IC1") (pin "H12") (pinfunction "IO_L20P_T3_A20_15_H12") (pintype "bidirectional"))
    )
    (net (code "195") (name "unconnected-(IC1E-IO_0_34-PadL5)") (class "Default")
      (node (ref "IC1") (pin "L5") (pinfunction "IO_0_34_L5") (pintype "bidirectional"))
    )
    (net (code "196") (name "unconnected-(IC1E-IO_L1N_T0_34-PadM4)") (class "Default")
      (node (ref "IC1") (pin "M4") (pinfunction "IO_L1N_T0_34_M4") (pintype "bidirectional"))
    )
    (net (code "197") (name "unconnected-(IC1E-IO_L1P_T0_34-PadL4)") (class "Default")
      (node (ref "IC1") (pin "L4") (pinfunction "IO_L1P_T0_34_L4") (pintype "bidirectional"))
    )
    (net (code "198") (name "unconnected-(IC1E-IO_L3N_T0_DQS_34-PadN3)") (class "Default")
      (node (ref "IC1") (pin "N3") (pinfunction "IO_L3N_T0_DQS_34_N3") (pintype "bidirectional"))
    )
    (net (code "199") (name "unconnected-(IC1E-IO_L3P_T0_DQS_34-PadN2)") (class "Default")
      (node (ref "IC1") (pin "N2") (pinfunction "IO_L3P_T0_DQS_34_N2") (pintype "bidirectional"))
    )
    (net (code "200") (name "unconnected-(IC1E-IO_L6N_T0_VREF_34-PadN4)") (class "Default")
      (node (ref "IC1") (pin "N4") (pinfunction "IO_L6N_T0_VREF_34_N4") (pintype "bidirectional"))
    )
    (net (code "201") (name "unconnected-(IC1E-IO_L6P_T0_34-PadM5)") (class "Default")
      (node (ref "IC1") (pin "M5") (pinfunction "IO_L6P_T0_34_M5") (pintype "bidirectional"))
    )
    (net (code "202") (name "unconnected-(IC1E-IO_L10P_T1_34-PadP5)") (class "Default")
      (node (ref "IC1") (pin "P5") (pinfunction "IO_L10P_T1_34_P5") (pintype "bidirectional"))
    )
    (net (code "203") (name "unconnected-(IC1F-IO_0_35-PadE6)") (class "Default")
      (node (ref "IC1") (pin "E6") (pinfunction "IO_0_35_E6") (pintype "bidirectional"))
    )
    (net (code "204") (name "unconnected-(IC1F-IO_25_35-PadK5)") (class "Default")
      (node (ref "IC1") (pin "K5") (pinfunction "IO_25_35_K5") (pintype "bidirectional"))
    )
    (net (code "205") (name "unconnected-(IC1F-IO_L1N_T0_AD4N_35-PadA7)") (class "Default")
      (node (ref "IC1") (pin "A7") (pinfunction "IO_L1N_T0_AD4N_35_A7") (pintype "bidirectional"))
    )
    (net (code "206") (name "unconnected-(IC1F-IO_L1P_T0_AD4P_35-PadB7)") (class "Default")
      (node (ref "IC1") (pin "B7") (pinfunction "IO_L1P_T0_AD4P_35_B7") (pintype "bidirectional"))
    )
    (net (code "207") (name "unconnected-(IC1F-IO_L6N_T0_VREF_35-PadD5)") (class "Default")
      (node (ref "IC1") (pin "D5") (pinfunction "IO_L6N_T0_VREF_35_D5") (pintype "bidirectional"))
    )
    (net (code "208") (name "unconnected-(IC1F-IO_L6P_T0_35-PadD6)") (class "Default")
      (node (ref "IC1") (pin "D6") (pinfunction "IO_L6P_T0_35_D6") (pintype "bidirectional"))
    )
    (net (code "209") (name "unconnected-(IC1F-IO_L11N_T1_SRCC_35-PadD3)") (class "Default")
      (node (ref "IC1") (pin "D3") (pinfunction "IO_L11N_T1_SRCC_35_D3") (pintype "bidirectional"))
    )
    (net (code "210") (name "unconnected-(IC1F-IO_L11P_T1_SRCC_35-PadE3)") (class "Default")
      (node (ref "IC1") (pin "E3") (pinfunction "IO_L11P_T1_SRCC_35_E3") (pintype "bidirectional"))
    )
    (net (code "211") (name "unconnected-(IC1F-IO_L13N_T2_MRCC_35-PadE5)") (class "Default")
      (node (ref "IC1") (pin "E5") (pinfunction "IO_L13N_T2_MRCC_35_E5") (pintype "bidirectional"))
    )
    (net (code "212") (name "unconnected-(IC1F-IO_L13P_T2_MRCC_35-PadF5)") (class "Default")
      (node (ref "IC1") (pin "F5") (pinfunction "IO_L13P_T2_MRCC_35_F5") (pintype "bidirectional"))
    )
    (net (code "213") (name "unconnected-(IC1F-IO_L16N_T2_35-PadG4)") (class "Default")
      (node (ref "IC1") (pin "G4") (pinfunction "IO_L16N_T2_35_G4") (pintype "bidirectional"))
    )
    (net (code "214") (name "unconnected-(IC1F-IO_L16P_T2_35-PadG5)") (class "Default")
      (node (ref "IC1") (pin "G5") (pinfunction "IO_L16P_T2_35_G5") (pintype "bidirectional"))
    )
    (net (code "215") (name "unconnected-(IC1F-IO_L18N_T2_35-PadH4)") (class "Default")
      (node (ref "IC1") (pin "H4") (pinfunction "IO_L18N_T2_35_H4") (pintype "bidirectional"))
    )
    (net (code "216") (name "unconnected-(IC1F-IO_L18P_T2_35-PadH5)") (class "Default")
      (node (ref "IC1") (pin "H5") (pinfunction "IO_L18P_T2_35_H5") (pintype "bidirectional"))
    )
    (net (code "217") (name "unconnected-(IC8-ACBUS7-Pad29)") (class "Default")
      (node (ref "IC8") (pin "29") (pinfunction "ACBUS7_29") (pintype "bidirectional"))
    )
    (net (code "218") (name "unconnected-(IC8-BCBUS0-Pad42)") (class "Default")
      (node (ref "IC8") (pin "42") (pinfunction "BCBUS0_42") (pintype "bidirectional"))
    )
    (net (code "219") (name "unconnected-(IC8-BCBUS1-Pad46)") (class "Default")
      (node (ref "IC8") (pin "46") (pinfunction "BCBUS1_46") (pintype "bidirectional"))
    )
    (net (code "220") (name "unconnected-(IC8-BCBUS2-Pad47)") (class "Default")
      (node (ref "IC8") (pin "47") (pinfunction "BCBUS2_47") (pintype "bidirectional"))
    )
    (net (code "221") (name "unconnected-(IC8-BCBUS3-Pad48)") (class "Default")
      (node (ref "IC8") (pin "48") (pinfunction "BCBUS3_48") (pintype "bidirectional"))
    )
    (net (code "222") (name "unconnected-(IC8-BCBUS4-Pad49)") (class "Default")
      (node (ref "IC8") (pin "49") (pinfunction "BCBUS4_49") (pintype "bidirectional"))
    )
    (net (code "223") (name "unconnected-(IC8-BCBUS5-Pad51)") (class "Default")
      (node (ref "IC8") (pin "51") (pinfunction "BCBUS5_51") (pintype "bidirectional"))
    )
    (net (code "224") (name "unconnected-(IC8-BCBUS6-Pad52)") (class "Default")
      (node (ref "IC8") (pin "52") (pinfunction "BCBUS6_52") (pintype "bidirectional"))
    )
    (net (code "225") (name "unconnected-(IC8-BCBUS7-Pad53)") (class "Default")
      (node (ref "IC8") (pin "53") (pinfunction "BCBUS7_53") (pintype "bidirectional"))
    )
    (net (code "226") (name "unconnected-(IC8-BDBUS4-Pad37)") (class "Default")
      (node (ref "IC8") (pin "37") (pinfunction "BDBUS4_37") (pintype "bidirectional"))
    )
    (net (code "227") (name "unconnected-(IC8-BDBUS5-Pad38)") (class "Default")
      (node (ref "IC8") (pin "38") (pinfunction "BDBUS5_38") (pintype "bidirectional"))
    )
    (net (code "228") (name "unconnected-(IC8-BDBUS6-Pad39)") (class "Default")
      (node (ref "IC8") (pin "39") (pinfunction "BDBUS6_39") (pintype "bidirectional"))
    )
    (net (code "229") (name "unconnected-(IC8-BDBUS7-Pad40)") (class "Default")
      (node (ref "IC8") (pin "40") (pinfunction "BDBUS7_40") (pintype "bidirectional"))
    )
    (net (code "230") (name "unconnected-(IC8-PWREN#-Pad54)") (class "Default")
      (node (ref "IC8") (pin "54") (pinfunction "PWREN#_54") (pintype "bidirectional"))
    )
    (net (code "231") (name "unconnected-(IC8-SUSPEND#-Pad30)") (class "Default")
      (node (ref "IC8") (pin "30") (pinfunction "SUSPEND#_30") (pintype "bidirectional"))
    )
    (net (code "232") (name "unconnected-(IC8-VREGIN-Pad44)") (class "Default")
      (node (ref "IC8") (pin "44") (pinfunction "VREGIN_44") (pintype "input"))
    )
    (net (code "233") (name "unconnected-(IC8-VREGOUT-Pad43)") (class "Default")
      (node (ref "IC8") (pin "43") (pinfunction "VREGOUT_43") (pintype "output"))
    )
  )
)
